# design.net
KiCad netlist of a schematic drawn in EasyEDA Pro
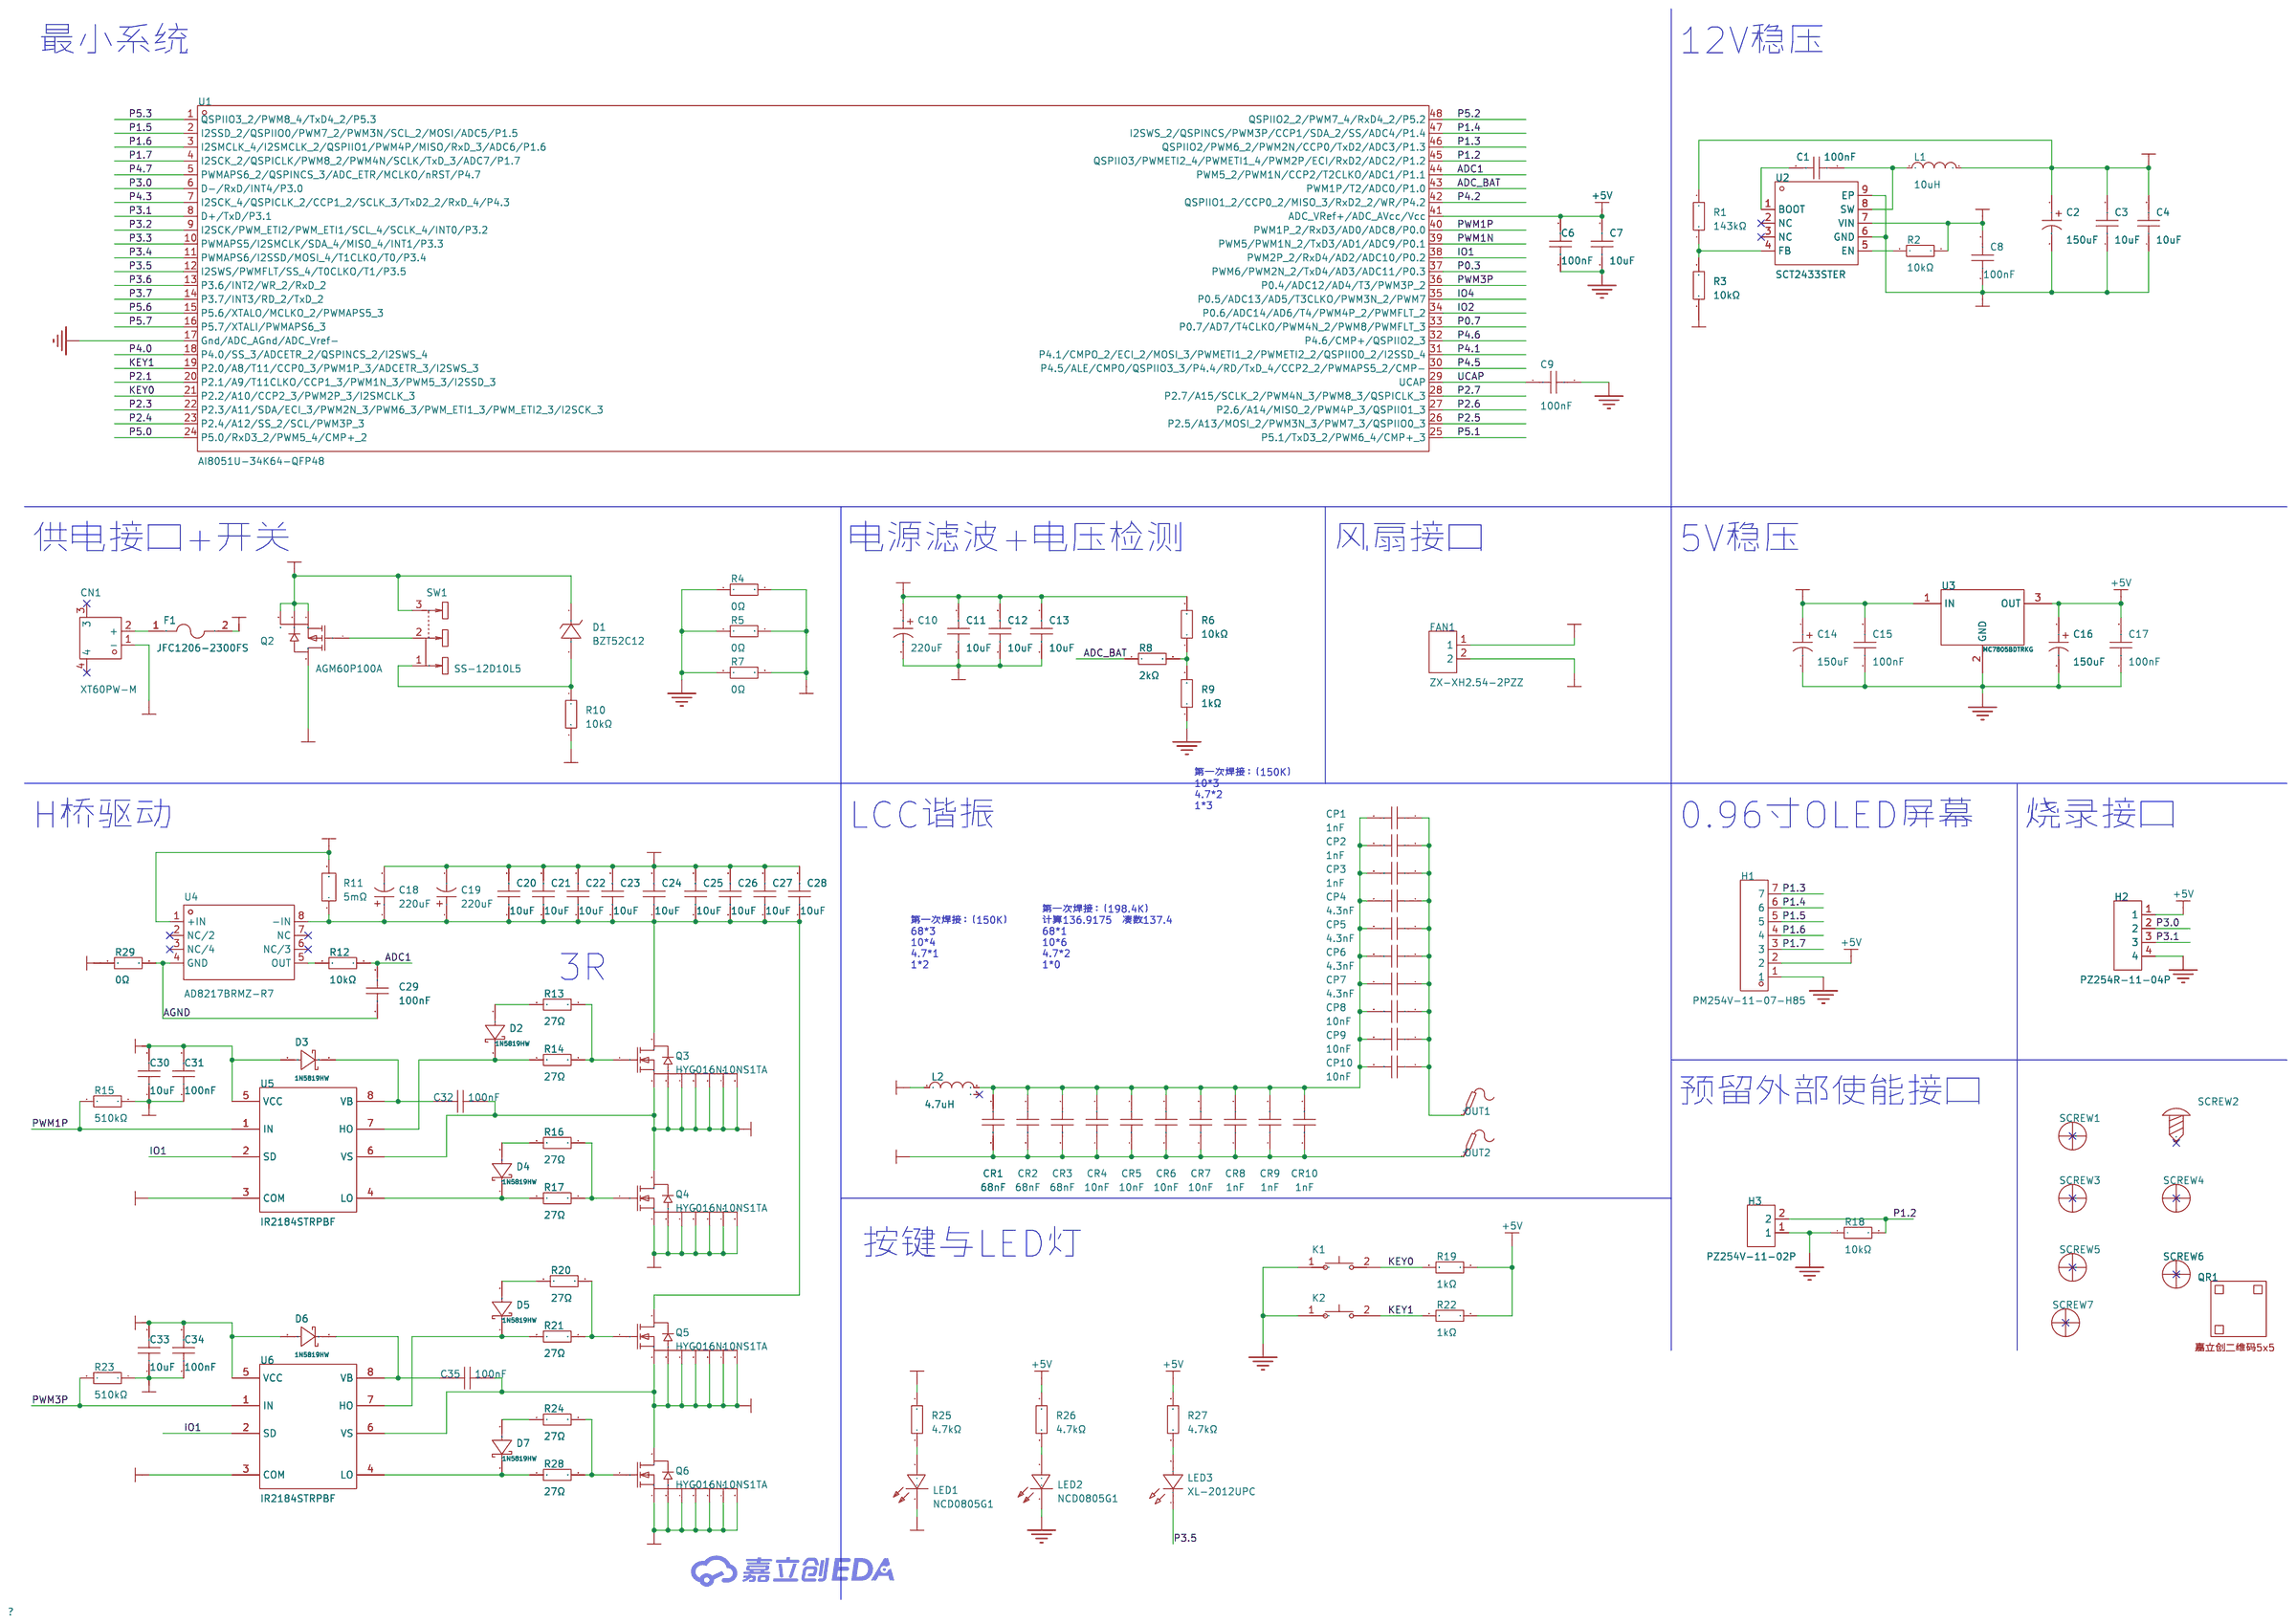
[diagram p0: schematic sheet]

(export (version "E")
  (design (tool "Eeschema 10.0.6"))
  (components
    (comp (ref "C1")
      (value "100nF")
      (fields
        (field (name "Manufacturer Part") "CC0603KRX7R9BB104")
        (field (name "Manufacturer") "YAGEO(国巨)")
      )
      (libsource (lib "easyedapro") (part "CC0603KRX7R9BB104"))
    )
    (comp (ref "C2")
      (value "150uF")
      (footprint "easyedapro:CAP-TH_BD6.3-P2.50-D0.5-FD")
      (description "容值:150uF;精度:±20%;额定电压:35V;纹波电流:2.55A;等效串联电阻:38mΩ;")
      (fields (field (name "Manufacturer Part") "HG1V157M0609PC") (field (name "Manufacturer") "HONOR(荣誉)"))
      (libsource (lib "easyedapro") (part "HG1V157M0609PC"))
    )
    (comp (ref "C3")
      (value "10uF")
      (footprint "easyedapro:C1206")
      (description "容值:10uF;精度:±10%;额定电压:50V;材质(温度系数):X5R;")
      (fields
        (field (name "Manufacturer Part") "GRM31CR61H106KA12L")
        (field (name "Manufacturer") "muRata(村田)")
      )
      (libsource (lib "easyedapro") (part "GRM31CR61H106KA12L"))
    )
    (comp (ref "C4")
      (value "10uF")
      (footprint "easyedapro:C1206")
      (description "容值:10uF;精度:±10%;额定电压:50V;材质(温度系数):X5R;")
      (fields
        (field (name "Manufacturer Part") "GRM31CR61H106KA12L")
        (field (name "Manufacturer") "muRata(村田)")
      )
      (libsource (lib "easyedapro") (part "GRM31CR61H106KA12L"))
    )
    (comp (ref "C6")
      (value "100nF")
      (footprint "easyedapro:C0603")
      (description "容值:100nF;精度:±10%;额定电压:50V;材质(温度系数):X7R;")
      (fields
        (field (name "Manufacturer Part") "CC0603KRX7R9BB104")
        (field (name "Manufacturer") "YAGEO(国巨)")
      )
      (libsource (lib "easyedapro") (part "CC0603KRX7R9BB104"))
    )
    (comp (ref "C7")
      (value "10uF")
      (footprint "easyedapro:C1206")
      (description "容值:10uF;精度:±10%;额定电压:50V;材质(温度系数):X5R;")
      (fields
        (field (name "Manufacturer Part") "GRM31CR61H106KA12L")
        (field (name "Manufacturer") "muRata(村田)")
      )
      (libsource (lib "easyedapro") (part "GRM31CR61H106KA12L"))
    )
    (comp (ref "C8")
      (value "100nF")
      (fields
        (field (name "Manufacturer Part") "CC0603KRX7R9BB104")
        (field (name "Manufacturer") "YAGEO(国巨)")
      )
      (libsource (lib "easyedapro") (part "CC0603KRX7R9BB104"))
    )
    (comp (ref "C9")
      (value "100nF")
      (footprint "easyedapro:C0603")
      (description "容值:100nF;精度:±10%;额定电压:50V;材质(温度系数):X7R;")
      (fields
        (field (name "Manufacturer Part") "CC0603KRX7R9BB104")
        (field (name "Manufacturer") "YAGEO(国巨)")
      )
      (libsource (lib "easyedapro") (part "CC0603KRX7R9BB104"))
    )
    (comp (ref "C10")
      (value "220uF")
      (footprint "easyedapro:CAP-TH_BD8.0-P3.50-D0.6-FD")
      (description "容值:220uF;精度:±20%;额定电压:35V;纹波电流:2.9A@100Hz;等效串联电阻(ESR):28mΩ@100kHz;类型:-;")
      (fields (field (name "Manufacturer Part") "PA35V220M8x8") (field (name "Manufacturer") "捷而瑞"))
      (libsource (lib "easyedapro") (part "PA35V220M8X8"))
    )
    (comp (ref "C11")
      (value "10uF")
      (footprint "easyedapro:C1206")
      (description "容值:10uF;精度:±10%;额定电压:50V;材质(温度系数):X5R;")
      (fields
        (field (name "Manufacturer Part") "GRM31CR61H106KA12L")
        (field (name "Manufacturer") "muRata(村田)")
      )
      (libsource (lib "easyedapro") (part "GRM31CR61H106KA12L"))
    )
    (comp (ref "C12")
      (value "10uF")
      (footprint "easyedapro:C1206")
      (description "容值:10uF;精度:±10%;额定电压:50V;材质(温度系数):X5R;")
      (fields
        (field (name "Manufacturer Part") "GRM31CR61H106KA12L")
        (field (name "Manufacturer") "muRata(村田)")
      )
      (libsource (lib "easyedapro") (part "GRM31CR61H106KA12L"))
    )
    (comp (ref "C13")
      (value "10uF")
      (footprint "easyedapro:C1206")
      (description "容值:10uF;精度:±10%;额定电压:50V;材质(温度系数):X5R;")
      (fields
        (field (name "Manufacturer Part") "GRM31CR61H106KA12L")
        (field (name "Manufacturer") "muRata(村田)")
      )
      (libsource (lib "easyedapro") (part "GRM31CR61H106KA12L"))
    )
    (comp (ref "C14")
      (value "150uF")
      (footprint "easyedapro:CAP-TH_BD6.3-P2.50-D0.5-FD")
      (description "容值:150uF;精度:±20%;额定电压:35V;纹波电流:2.55A;等效串联电阻:38mΩ;")
      (fields (field (name "Manufacturer Part") "HG1V157M0609PC") (field (name "Manufacturer") "HONOR(荣誉)"))
      (libsource (lib "easyedapro") (part "HG1V157M0609PC"))
    )
    (comp (ref "C15")
      (value "100nF")
      (footprint "easyedapro:C0603")
      (description "容值:100nF;精度:±10%;额定电压:50V;材质(温度系数):X7R;")
      (fields
        (field (name "Manufacturer Part") "CC0603KRX7R9BB104")
        (field (name "Manufacturer") "YAGEO(国巨)")
      )
      (libsource (lib "easyedapro") (part "CC0603KRX7R9BB104"))
    )
    (comp (ref "C16")
      (value "150uF")
      (footprint "easyedapro:CAP-TH_BD6.3-P2.50-D0.5-FD")
      (description "容值:150uF;精度:±20%;额定电压:35V;纹波电流:2.55A;等效串联电阻:38mΩ;")
      (fields (field (name "Manufacturer Part") "HG1V157M0609PC") (field (name "Manufacturer") "HONOR(荣誉)"))
      (libsource (lib "easyedapro") (part "HG1V157M0609PC"))
    )
    (comp (ref "C17")
      (value "100nF")
      (footprint "easyedapro:C0603")
      (description "容值:100nF;精度:±10%;额定电压:50V;材质(温度系数):X7R;")
      (fields
        (field (name "Manufacturer Part") "CC0603KRX7R9BB104")
        (field (name "Manufacturer") "YAGEO(国巨)")
      )
      (libsource (lib "easyedapro") (part "CC0603KRX7R9BB104"))
    )
    (comp (ref "C18")
      (value "220uF")
      (footprint "easyedapro:CAP-TH_BD8.0-P3.50-D0.6-FD")
      (description "容值:220uF;精度:±20%;额定电压:35V;纹波电流:2.9A@100Hz;等效串联电阻(ESR):28mΩ@100kHz;类型:-;")
      (fields (field (name "Manufacturer Part") "PA35V220M8x8") (field (name "Manufacturer") "捷而瑞"))
      (libsource (lib "easyedapro") (part "PA35V220M8X8"))
    )
    (comp (ref "C19")
      (value "220uF")
      (footprint "easyedapro:CAP-TH_BD8.0-P3.50-D0.6-FD")
      (description "容值:220uF;精度:±20%;额定电压:35V;纹波电流:2.9A@100Hz;等效串联电阻(ESR):28mΩ@100kHz;类型:-;")
      (fields (field (name "Manufacturer Part") "PA35V220M8x8") (field (name "Manufacturer") "捷而瑞"))
      (libsource (lib "easyedapro") (part "PA35V220M8X8"))
    )
    (comp (ref "C20")
      (value "10uF")
      (footprint "easyedapro:C1206")
      (description "容值:10uF;精度:±10%;额定电压:50V;材质(温度系数):X5R;")
      (fields
        (field (name "Manufacturer Part") "GRM31CR61H106KA12L")
        (field (name "Manufacturer") "muRata(村田)")
      )
      (libsource (lib "easyedapro") (part "GRM31CR61H106KA12L"))
    )
    (comp (ref "C21")
      (value "10uF")
      (footprint "easyedapro:C1206")
      (description "容值:10uF;精度:±10%;额定电压:50V;材质(温度系数):X5R;")
      (fields
        (field (name "Manufacturer Part") "GRM31CR61H106KA12L")
        (field (name "Manufacturer") "muRata(村田)")
      )
      (libsource (lib "easyedapro") (part "GRM31CR61H106KA12L"))
    )
    (comp (ref "C22")
      (value "10uF")
      (footprint "easyedapro:C1206")
      (description "容值:10uF;精度:±10%;额定电压:50V;材质(温度系数):X5R;")
      (fields
        (field (name "Manufacturer Part") "GRM31CR61H106KA12L")
        (field (name "Manufacturer") "muRata(村田)")
      )
      (libsource (lib "easyedapro") (part "GRM31CR61H106KA12L"))
    )
    (comp (ref "C23")
      (value "10uF")
      (footprint "easyedapro:C1206")
      (description "容值:10uF;精度:±10%;额定电压:50V;材质(温度系数):X5R;")
      (fields
        (field (name "Manufacturer Part") "GRM31CR61H106KA12L")
        (field (name "Manufacturer") "muRata(村田)")
      )
      (libsource (lib "easyedapro") (part "GRM31CR61H106KA12L"))
    )
    (comp (ref "C24")
      (value "10uF")
      (footprint "easyedapro:C1206")
      (description "容值:10uF;精度:±10%;额定电压:50V;材质(温度系数):X5R;")
      (fields
        (field (name "Manufacturer Part") "GRM31CR61H106KA12L")
        (field (name "Manufacturer") "muRata(村田)")
      )
      (libsource (lib "easyedapro") (part "GRM31CR61H106KA12L"))
    )
    (comp (ref "C25")
      (value "10uF")
      (footprint "easyedapro:C1206")
      (description "容值:10uF;精度:±10%;额定电压:50V;材质(温度系数):X5R;")
      (fields
        (field (name "Manufacturer Part") "GRM31CR61H106KA12L")
        (field (name "Manufacturer") "muRata(村田)")
      )
      (libsource (lib "easyedapro") (part "GRM31CR61H106KA12L"))
    )
    (comp (ref "C26")
      (value "10uF")
      (footprint "easyedapro:C1206")
      (description "容值:10uF;精度:±10%;额定电压:50V;材质(温度系数):X5R;")
      (fields
        (field (name "Manufacturer Part") "GRM31CR61H106KA12L")
        (field (name "Manufacturer") "muRata(村田)")
      )
      (libsource (lib "easyedapro") (part "GRM31CR61H106KA12L"))
    )
    (comp (ref "C27")
      (value "10uF")
      (footprint "easyedapro:C1206")
      (description "容值:10uF;精度:±10%;额定电压:50V;材质(温度系数):X5R;")
      (fields
        (field (name "Manufacturer Part") "GRM31CR61H106KA12L")
        (field (name "Manufacturer") "muRata(村田)")
      )
      (libsource (lib "easyedapro") (part "GRM31CR61H106KA12L"))
    )
    (comp (ref "C28")
      (value "10uF")
      (footprint "easyedapro:C1206")
      (description "容值:10uF;精度:±10%;额定电压:50V;材质(温度系数):X5R;")
      (fields
        (field (name "Manufacturer Part") "GRM31CR61H106KA12L")
        (field (name "Manufacturer") "muRata(村田)")
      )
      (libsource (lib "easyedapro") (part "GRM31CR61H106KA12L"))
    )
    (comp (ref "C29")
      (value "100nF")
      (footprint "easyedapro:C0603")
      (description "容值:100nF;精度:±10%;额定电压:50V;材质(温度系数):X7R;")
      (fields
        (field (name "Manufacturer Part") "CC0603KRX7R9BB104")
        (field (name "Manufacturer") "YAGEO(国巨)")
      )
      (libsource (lib "easyedapro") (part "CC0603KRX7R9BB104"))
    )
    (comp (ref "C30")
      (value "10uF")
      (footprint "easyedapro:C1206")
      (description "容值:10uF;精度:±10%;额定电压:50V;材质(温度系数):X5R;")
      (fields
        (field (name "Manufacturer Part") "GRM31CR61H106KA12L")
        (field (name "Manufacturer") "muRata(村田)")
      )
      (libsource (lib "easyedapro") (part "GRM31CR61H106KA12L"))
    )
    (comp (ref "C31")
      (value "100nF")
      (footprint "easyedapro:C0603")
      (description "容值:100nF;精度:±10%;额定电压:50V;材质(温度系数):X7R;")
      (fields
        (field (name "Manufacturer Part") "CC0603KRX7R9BB104")
        (field (name "Manufacturer") "YAGEO(国巨)")
      )
      (libsource (lib "easyedapro") (part "CC0603KRX7R9BB104"))
    )
    (comp (ref "C32")
      (value "100nF")
      (footprint "easyedapro:C0603")
      (description "容值:100nF;精度:±10%;额定电压:50V;材质(温度系数):X7R;")
      (fields
        (field (name "Manufacturer Part") "CC0603KRX7R9BB104")
        (field (name "Manufacturer") "YAGEO(国巨)")
      )
      (libsource (lib "easyedapro") (part "CC0603KRX7R9BB104"))
    )
    (comp (ref "C33")
      (value "10uF")
      (footprint "easyedapro:C1206")
      (description "容值:10uF;精度:±10%;额定电压:50V;材质(温度系数):X5R;")
      (fields
        (field (name "Manufacturer Part") "GRM31CR61H106KA12L")
        (field (name "Manufacturer") "muRata(村田)")
      )
      (libsource (lib "easyedapro") (part "GRM31CR61H106KA12L"))
    )
    (comp (ref "C34")
      (value "100nF")
      (footprint "easyedapro:C0603")
      (description "容值:100nF;精度:±10%;额定电压:50V;材质(温度系数):X7R;")
      (fields
        (field (name "Manufacturer Part") "CC0603KRX7R9BB104")
        (field (name "Manufacturer") "YAGEO(国巨)")
      )
      (libsource (lib "easyedapro") (part "CC0603KRX7R9BB104"))
    )
    (comp (ref "C35")
      (value "100nF")
      (footprint "easyedapro:C0603")
      (description "容值:100nF;精度:±10%;额定电压:50V;材质(温度系数):X7R;")
      (fields
        (field (name "Manufacturer Part") "CC0603KRX7R9BB104")
        (field (name "Manufacturer") "YAGEO(国巨)")
      )
      (libsource (lib "easyedapro") (part "CC0603KRX7R9BB104"))
    )
    (comp (ref "CN1")
      (value "XT60PW-M")
      (footprint "easyedapro:CONN-TH_XT60PW-M")
      (description "类别:-;类型1:-;")
      (fields (field (name "Manufacturer") "AMASS(艾迈斯)"))
      (libsource (lib "easyedapro") (part "XT60PW-M"))
    )
    (comp (ref "CP1")
      (value "1nF")
      (footprint "easyedapro:C1206")
      (description "容值:1nF;精度:±5%;额定电压:1kV;材质(温度系数):NP0;")
      (fields
        (field (name "Manufacturer Part") "CC1206JKNPOCBN102")
        (field (name "Manufacturer") "YAGEO(国巨)")
      )
      (libsource (lib "easyedapro") (part "CC1206JKNPOCBN102"))
    )
    (comp (ref "CP2")
      (value "1nF")
      (footprint "easyedapro:C1206")
      (description "容值:1nF;精度:±5%;额定电压:1kV;材质(温度系数):NP0;")
      (fields
        (field (name "Manufacturer Part") "CC1206JKNPOCBN102")
        (field (name "Manufacturer") "YAGEO(国巨)")
      )
      (libsource (lib "easyedapro") (part "CC1206JKNPOCBN102"))
    )
    (comp (ref "CP3")
      (value "1nF")
      (footprint "easyedapro:C1206")
      (description "容值:1nF;精度:±5%;额定电压:1kV;材质(温度系数):NP0;")
      (fields
        (field (name "Manufacturer Part") "CC1206JKNPOCBN102")
        (field (name "Manufacturer") "YAGEO(国巨)")
      )
      (libsource (lib "easyedapro") (part "CC1206JKNPOCBN102"))
    )
    (comp (ref "CP4")
      (value "4.3nF")
      (footprint "easyedapro:C1206")
      (description "容值:4.3nF;精度:±5%;额定电压:100V;材质(温度系数):C0G;")
      (fields
        (field (name "Manufacturer Part") "GRM3195C2A432JA01D")
        (field (name "Manufacturer") "muRata(村田)")
      )
      (libsource (lib "easyedapro") (part "GRM3195C2A432JA01D"))
    )
    (comp (ref "CP5")
      (value "4.3nF")
      (footprint "easyedapro:C1206")
      (description "容值:4.3nF;精度:±5%;额定电压:100V;材质(温度系数):C0G;")
      (fields
        (field (name "Manufacturer Part") "GRM3195C2A432JA01D")
        (field (name "Manufacturer") "muRata(村田)")
      )
      (libsource (lib "easyedapro") (part "GRM3195C2A432JA01D"))
    )
    (comp (ref "CP6")
      (value "4.3nF")
      (footprint "easyedapro:C1206")
      (description "容值:4.3nF;精度:±5%;额定电压:100V;材质(温度系数):C0G;")
      (fields
        (field (name "Manufacturer Part") "GRM3195C2A432JA01D")
        (field (name "Manufacturer") "muRata(村田)")
      )
      (libsource (lib "easyedapro") (part "GRM3195C2A432JA01D"))
    )
    (comp (ref "CP7")
      (value "4.3nF")
      (footprint "easyedapro:C1206")
      (description "容值:4.3nF;精度:±5%;额定电压:100V;材质(温度系数):C0G;")
      (fields
        (field (name "Manufacturer Part") "GRM3195C2A432JA01D")
        (field (name "Manufacturer") "muRata(村田)")
      )
      (libsource (lib "easyedapro") (part "GRM3195C2A432JA01D"))
    )
    (comp (ref "CP8")
      (value "10nF")
      (footprint "easyedapro:C1206")
      (description "容值:10nF;精度:±5%;额定电压:100V;材质(温度系数):C0G;")
      (fields
        (field (name "Manufacturer Part") "GCM3195C2A103JA16D")
        (field (name "Manufacturer") "muRata(村田)")
      )
      (libsource (lib "easyedapro") (part "GCM3195C2A103JA16D"))
    )
    (comp (ref "CP9")
      (value "10nF")
      (footprint "easyedapro:C1206")
      (description "容值:10nF;精度:±5%;额定电压:100V;材质(温度系数):C0G;")
      (fields
        (field (name "Manufacturer Part") "GCM3195C2A103JA16D")
        (field (name "Manufacturer") "muRata(村田)")
      )
      (libsource (lib "easyedapro") (part "GCM3195C2A103JA16D"))
    )
    (comp (ref "CP10")
      (value "10nF")
      (footprint "easyedapro:C1206")
      (description "容值:10nF;精度:±5%;额定电压:100V;材质(温度系数):C0G;")
      (fields
        (field (name "Manufacturer Part") "GCM3195C2A103JA16D")
        (field (name "Manufacturer") "muRata(村田)")
      )
      (libsource (lib "easyedapro") (part "GCM3195C2A103JA16D"))
    )
    (comp (ref "CR1")
      (value "68nF")
      (footprint "easyedapro:C1206")
      (description "容值:68nF;精度:±5%;额定电压:100V;温度系数:C0G;")
      (fields (field (name "Manufacturer Part") "C3216C0G2A683JT000E") (field (name "Manufacturer") "TDK"))
      (libsource (lib "easyedapro") (part "C3216C0G2A683JT000E"))
    )
    (comp (ref "CR2")
      (value "68nF")
      (footprint "easyedapro:C1206")
      (description "容值:68nF;精度:±5%;额定电压:100V;温度系数:C0G;")
      (fields (field (name "Manufacturer Part") "C3216C0G2A683JT000E") (field (name "Manufacturer") "TDK"))
      (libsource (lib "easyedapro") (part "C3216C0G2A683JT000E"))
    )
    (comp (ref "CR3")
      (value "68nF")
      (footprint "easyedapro:C1206")
      (description "容值:68nF;精度:±5%;额定电压:100V;温度系数:C0G;")
      (fields (field (name "Manufacturer Part") "C3216C0G2A683JT000E") (field (name "Manufacturer") "TDK"))
      (libsource (lib "easyedapro") (part "C3216C0G2A683JT000E"))
    )
    (comp (ref "CR4")
      (value "10nF")
      (footprint "easyedapro:C1206")
      (description "容值:10nF;精度:±5%;额定电压:100V;材质(温度系数):C0G;")
      (fields
        (field (name "Manufacturer Part") "GCM3195C2A103JA16D")
        (field (name "Manufacturer") "muRata(村田)")
      )
      (libsource (lib "easyedapro") (part "GCM3195C2A103JA16D"))
    )
    (comp (ref "CR5")
      (value "10nF")
      (footprint "easyedapro:C1206")
      (description "容值:10nF;精度:±5%;额定电压:100V;材质(温度系数):C0G;")
      (fields
        (field (name "Manufacturer Part") "GCM3195C2A103JA16D")
        (field (name "Manufacturer") "muRata(村田)")
      )
      (libsource (lib "easyedapro") (part "GCM3195C2A103JA16D"))
    )
    (comp (ref "CR6")
      (value "10nF")
      (footprint "easyedapro:C1206")
      (description "容值:10nF;精度:±5%;额定电压:100V;材质(温度系数):C0G;")
      (fields
        (field (name "Manufacturer Part") "GCM3195C2A103JA16D")
        (field (name "Manufacturer") "muRata(村田)")
      )
      (libsource (lib "easyedapro") (part "GCM3195C2A103JA16D"))
    )
    (comp (ref "CR7")
      (value "10nF")
      (footprint "easyedapro:C1206")
      (description "容值:10nF;精度:±5%;额定电压:100V;材质(温度系数):C0G;")
      (fields
        (field (name "Manufacturer Part") "GCM3195C2A103JA16D")
        (field (name "Manufacturer") "muRata(村田)")
      )
      (libsource (lib "easyedapro") (part "GCM3195C2A103JA16D"))
    )
    (comp (ref "CR8")
      (value "1nF")
      (footprint "easyedapro:C1206")
      (description "容值:1nF;精度:±5%;额定电压:1kV;材质(温度系数):NP0;")
      (fields
        (field (name "Manufacturer Part") "CC1206JKNPOCBN102")
        (field (name "Manufacturer") "YAGEO(国巨)")
      )
      (libsource (lib "easyedapro") (part "CC1206JKNPOCBN102"))
    )
    (comp (ref "CR9")
      (value "1nF")
      (footprint "easyedapro:C1206")
      (description "容值:1nF;精度:±5%;额定电压:1kV;材质(温度系数):NP0;")
      (fields
        (field (name "Manufacturer Part") "CC1206JKNPOCBN102")
        (field (name "Manufacturer") "YAGEO(国巨)")
      )
      (libsource (lib "easyedapro") (part "CC1206JKNPOCBN102"))
    )
    (comp (ref "CR10")
      (value "1nF")
      (footprint "easyedapro:C1206")
      (description "容值:1nF;精度:±5%;额定电压:1kV;材质(温度系数):NP0;")
      (fields
        (field (name "Manufacturer Part") "CC1206JKNPOCBN102")
        (field (name "Manufacturer") "YAGEO(国巨)")
      )
      (libsource (lib "easyedapro") (part "CC1206JKNPOCBN102"))
    )
    (comp (ref "D1")
      (value "BZT52C12")
      (footprint "easyedapro:SOD-123_L2.7-W1.6-LS3.7-RD")
      (description "二极管配置:独立式;稳压值(标称值):12V;稳压值(范围):11.4V~12.6V;功率(Pd):500mW;")
      (fields (field (name "Manufacturer") "宏迦橙"))
      (libsource (lib "easyedapro") (part "BZT52C12_C19077410"))
    )
    (comp (ref "D2")
      (value "1N5819HW")
      (footprint "easyedapro:SOD-123_L2.7-W1.6-LS3.8-RD")
      (description "正向压降(Vf):580mV@1.0A;直流反向耐压(Vr):40V;整流电流:1A;")
      (fields (field (name "Manufacturer") "GOODWORK(固得沃克)"))
      (libsource (lib "easyedapro") (part "1N5819HW_C41431974"))
    )
    (comp (ref "D3")
      (value "1N5819HW")
      (footprint "easyedapro:SOD-123_L2.7-W1.6-LS3.8-RD")
      (description "正向压降(Vf):580mV@1.0A;直流反向耐压(Vr):40V;整流电流:1A;")
      (fields (field (name "Manufacturer") "GOODWORK(固得沃克)"))
      (libsource (lib "easyedapro") (part "1N5819HW_C41431974"))
    )
    (comp (ref "D4")
      (value "1N5819HW")
      (footprint "easyedapro:SOD-123_L2.7-W1.6-LS3.8-RD")
      (description "正向压降(Vf):580mV@1.0A;直流反向耐压(Vr):40V;整流电流:1A;")
      (fields (field (name "Manufacturer") "GOODWORK(固得沃克)"))
      (libsource (lib "easyedapro") (part "1N5819HW_C41431974"))
    )
    (comp (ref "D5")
      (value "1N5819HW")
      (footprint "easyedapro:SOD-123_L2.7-W1.6-LS3.8-RD")
      (description "正向压降(Vf):580mV@1.0A;直流反向耐压(Vr):40V;整流电流:1A;")
      (fields (field (name "Manufacturer") "GOODWORK(固得沃克)"))
      (libsource (lib "easyedapro") (part "1N5819HW_C41431974"))
    )
    (comp (ref "D6")
      (value "1N5819HW")
      (footprint "easyedapro:SOD-123_L2.7-W1.6-LS3.8-RD")
      (description "正向压降(Vf):580mV@1.0A;直流反向耐压(Vr):40V;整流电流:1A;")
      (fields (field (name "Manufacturer") "GOODWORK(固得沃克)"))
      (libsource (lib "easyedapro") (part "1N5819HW_C41431974"))
    )
    (comp (ref "D7")
      (value "1N5819HW")
      (footprint "easyedapro:SOD-123_L2.7-W1.6-LS3.8-RD")
      (description "正向压降(Vf):580mV@1.0A;直流反向耐压(Vr):40V;整流电流:1A;")
      (fields (field (name "Manufacturer") "GOODWORK(固得沃克)"))
      (libsource (lib "easyedapro") (part "1N5819HW_C41431974"))
    )
    (comp (ref "F1")
      (value "JFC1206-2300FS")
      (footprint "easyedapro:F1206")
      (description "类型:贴片式保险丝;额定电流:30A;额定电压 (AC):32V;额定电压:32V;分断能力:150A;")
      (fields (field (name "Manufacturer") "JDTfuse(集电通)"))
      (libsource (lib "easyedapro") (part "JFC1206-2300FS"))
    )
    (comp (ref "FAN1")
      (value "ZX-XH2.54-2PZZ")
      (footprint "easyedapro:CONN-TH_2P-P2.50_HX25003-2A")
      (fields (field (name "Manufacturer") "Megastar(兆星)"))
      (libsource (lib "easyedapro") (part "ZX-XH2.54-2PZZ"))
    )
    (comp (ref "H1")
      (value "PM254V-11-07-H85")
      (footprint "easyedapro:HDR-TH_7P-P2.54-V-F")
      (fields (field (name "Manufacturer") "XFCN(兴飞)"))
      (libsource (lib "easyedapro") (part "PM254V-11-07-H85"))
    )
    (comp (ref "H2")
      (value "PZ254R-11-04P")
      (footprint "easyedapro:HDR-TH_4P-P2.54-H-M-W10.4")
      (fields (field (name "Manufacturer") "XFCN(兴飞)"))
      (libsource (lib "easyedapro") (part "PZ254R-11-04P"))
    )
    (comp (ref "H3")
      (value "PZ254V-11-02P")
      (footprint "easyedapro:HDR-TH_2P-P2.54-V-M")
      (fields (field (name "Manufacturer") "XFCN(兴飞)"))
      (libsource (lib "easyedapro") (part "PZ254V-11-02P"))
    )
    (comp (ref "K1")
      (value "TS3625A")
      (footprint "easyedapro:KEY-SMD_L6.0-W3.5-LS8.4")
      (fields (field (name "Manufacturer") "SHOU HAN(首韩)"))
      (libsource (lib "easyedapro") (part "TS3625A"))
    )
    (comp (ref "K2")
      (value "TS3625A")
      (footprint "easyedapro:KEY-SMD_L6.0-W3.5-LS8.4")
      (fields (field (name "Manufacturer") "SHOU HAN(首韩)"))
      (libsource (lib "easyedapro") (part "TS3625A"))
    )
    (comp (ref "L1")
      (value "10uH")
      (footprint "easyedapro:IND-SMD_L4.1-W4.1_FTC404020S")
      (description "电感值:10uH;精度:±20%;额定电流:3.4A;饱和电流(Isat):4.9A;类型:一体成型电感;")
      (fields
        (field (name "Manufacturer Part") "FTC404020S100MGCA")
        (field (name "Manufacturer") "cjiang(长江微电)")
      )
      (libsource (lib "easyedapro") (part "FTC404020S100MGCA"))
    )
    (comp (ref "L2")
      (value "4.7uH")
      (footprint "easyedapro:IND-SMD_3P-L28.0-W19.0-LS27.0")
      (description "电感值:4.7uH;精度:±20%;额定电流:47.5A;饱和电流(Isat):49.5A;类型:扁平线大电流电感;")
      (fields
        (field (name "Manufacturer Part") "RSBPQ2918-4R7M")
        (field (name "Manufacturer") "Ruishen(瑞申电子)")
      )
      (libsource (lib "easyedapro") (part "RSBPQ2918-4R7M"))
    )
    (comp (ref "LED1")
      (value "NCD0805G1")
      (footprint "easyedapro:LED0805-R-RD")
      (fields (field (name "Manufacturer") "国星光电"))
      (libsource (lib "easyedapro") (part "FC-2012UGK-520D5"))
    )
    (comp (ref "LED2")
      (value "NCD0805G1")
      (footprint "easyedapro:LED0805-R-RD")
      (fields (field (name "Manufacturer") "国星光电"))
      (libsource (lib "easyedapro") (part "FC-2012UGK-520D5"))
    )
    (comp (ref "LED3")
      (value "XL-2012UPC")
      (footprint "easyedapro:LED0805-RD_PINK")
      (fields (field (name "Manufacturer") "XINGLIGHT(成兴光)"))
      (libsource (lib "easyedapro") (part "XL-2012UPC"))
    )
    (comp (ref "OUT1")
      (value "~")
      (footprint "easyedapro:Test-Point-0.5mm")
      (description "Test Point 测试点")
      (libsource (lib "easyedapro") (part "Test-Point"))
    )
    (comp (ref "OUT2")
      (value "~")
      (footprint "easyedapro:Test-Point-0.5mm")
      (description "Test Point 测试点")
      (libsource (lib "easyedapro") (part "Test-Point"))
    )
    (comp (ref "Q2")
      (value "AGM60P100A")
      (footprint "easyedapro:TDSON-8_L5.9-W5.2-P1.27-BL")
      (fields (field (name "Manufacturer") "AGM-Semi(芯控源)"))
      (libsource (lib "easyedapro") (part "AGM60P100A"))
    )
    (comp (ref "Q3")
      (value "HYG016N10NS1TA")
      (footprint "easyedapro:TOLL-8_L10.4-W9.9-P1.20-LS11.7-BL")
      (fields (field (name "Manufacturer") "HUAYI(华羿微)"))
      (libsource (lib "easyedapro") (part "HYG016N10NS1TA"))
    )
    (comp (ref "Q4")
      (value "HYG016N10NS1TA")
      (footprint "easyedapro:TOLL-8_L10.4-W9.9-P1.20-LS11.7-BL")
      (fields (field (name "Manufacturer") "HUAYI(华羿微)"))
      (libsource (lib "easyedapro") (part "HYG016N10NS1TA"))
    )
    (comp (ref "Q5")
      (value "HYG016N10NS1TA")
      (footprint "easyedapro:TOLL-8_L10.4-W9.9-P1.20-LS11.7-BL")
      (fields (field (name "Manufacturer") "HUAYI(华羿微)"))
      (libsource (lib "easyedapro") (part "HYG016N10NS1TA"))
    )
    (comp (ref "Q6")
      (value "HYG016N10NS1TA")
      (footprint "easyedapro:TOLL-8_L10.4-W9.9-P1.20-LS11.7-BL")
      (fields (field (name "Manufacturer") "HUAYI(华羿微)"))
      (libsource (lib "easyedapro") (part "HYG016N10NS1TA"))
    )
    (comp (ref "QR1")
      (value "~")
      (footprint "easyedapro:JLC-QRCODE-5x5")
      (libsource (lib "easyedapro") (part "嘉立创二维码5x5"))
    )
    (comp (ref "R1")
      (value "143kΩ")
      (footprint "easyedapro:R0603")
      (description "电阻类型:厚膜电阻;阻值:143kΩ;精度:±1%;功率:100mW;最大工作电压:75V;温度系数:±100ppm/°C;")
      (fields
        (field (name "Manufacturer Part") "0603WAF1433T5E")
        (field (name "Manufacturer") "UNI-ROYAL(厚声)")
      )
      (libsource (lib "easyedapro") (part "0603WAF1433T5E"))
    )
    (comp (ref "R2")
      (value "10kΩ")
      (footprint "easyedapro:R0603")
      (description "电阻类型:厚膜电阻;阻值:10kΩ;精度:±1%;功率:100mW;最大工作电压:75V;温度系数:±100ppm/°C;")
      (fields
        (field (name "Manufacturer Part") "0603WAF1002T5E")
        (field (name "Manufacturer") "UNI-ROYAL(厚声)")
      )
      (libsource (lib "easyedapro") (part "0603WAF1002T5E"))
    )
    (comp (ref "R3")
      (value "10kΩ")
      (footprint "easyedapro:R0603")
      (description "电阻类型:厚膜电阻;阻值:10kΩ;精度:±1%;功率:100mW;最大工作电压:75V;温度系数:±100ppm/°C;")
      (fields
        (field (name "Manufacturer Part") "0603WAF1002T5E")
        (field (name "Manufacturer") "UNI-ROYAL(厚声)")
      )
      (libsource (lib "easyedapro") (part "0603WAF1002T5E"))
    )
    (comp (ref "R4")
      (value "0Ω")
      (footprint "easyedapro:R0603")
      (description "电阻类型:厚膜电阻;阻值:0Ω;精度:±1%;功率:100mW;最大工作电压:75V;")
      (fields
        (field (name "Manufacturer Part") "0603WAF0000T5E")
        (field (name "Manufacturer") "UNI-ROYAL(厚声)")
      )
      (libsource (lib "easyedapro") (part "0603WAF0000T5E"))
    )
    (comp (ref "R5")
      (value "0Ω")
      (footprint "easyedapro:R0603")
      (description "电阻类型:厚膜电阻;阻值:0Ω;精度:±1%;功率:100mW;最大工作电压:75V;")
      (fields
        (field (name "Manufacturer Part") "0603WAF0000T5E")
        (field (name "Manufacturer") "UNI-ROYAL(厚声)")
      )
      (libsource (lib "easyedapro") (part "0603WAF0000T5E"))
    )
    (comp (ref "R6")
      (value "10kΩ")
      (footprint "easyedapro:R0603")
      (description "电阻类型:厚膜电阻;阻值:10kΩ;精度:±1%;功率:100mW;最大工作电压:75V;温度系数:±100ppm/°C;")
      (fields
        (field (name "Manufacturer Part") "0603WAF1002T5E")
        (field (name "Manufacturer") "UNI-ROYAL(厚声)")
      )
      (libsource (lib "easyedapro") (part "0603WAF1002T5E"))
    )
    (comp (ref "R7")
      (value "0Ω")
      (footprint "easyedapro:R0603")
      (description "电阻类型:厚膜电阻;阻值:0Ω;精度:±1%;功率:100mW;最大工作电压:75V;")
      (fields
        (field (name "Manufacturer Part") "0603WAF0000T5E")
        (field (name "Manufacturer") "UNI-ROYAL(厚声)")
      )
      (libsource (lib "easyedapro") (part "0603WAF0000T5E"))
    )
    (comp (ref "R8")
      (value "2kΩ")
      (footprint "easyedapro:R0603")
      (description "电阻类型:厚膜电阻;阻值:2kΩ;精度:±1%;功率:100mW;最大工作电压:75V;温度系数:±100ppm/°C;")
      (fields
        (field (name "Manufacturer Part") "0603WAF2001T5E")
        (field (name "Manufacturer") "UNI-ROYAL(厚声)")
      )
      (libsource (lib "easyedapro") (part "0603WAF2001T5E"))
    )
    (comp (ref "R9")
      (value "1kΩ")
      (footprint "easyedapro:R0603")
      (description "电阻类型:厚膜电阻;阻值:1kΩ;精度:±1%;功率:100mW;最大工作电压:75V;温度系数:±100ppm/°C;")
      (fields
        (field (name "Manufacturer Part") "0603WAF1001T5E")
        (field (name "Manufacturer") "UNI-ROYAL(厚声)")
      )
      (libsource (lib "easyedapro") (part "0603WAF1001T5E"))
    )
    (comp (ref "R10")
      (value "10kΩ")
      (footprint "easyedapro:R0603")
      (description "电阻类型:厚膜电阻;阻值:10kΩ;精度:±1%;功率:100mW;最大工作电压:75V;温度系数:±100ppm/°C;")
      (fields
        (field (name "Manufacturer Part") "0603WAF1002T5E")
        (field (name "Manufacturer") "UNI-ROYAL(厚声)")
      )
      (libsource (lib "easyedapro") (part "0603WAF1002T5E"))
    )
    (comp (ref "R11")
      (value "5mΩ")
      (footprint "easyedapro:RES-SMD_L10.0-W5.2")
      (description "阻值:5mΩ;功率:5W;")
      (fields
        (field (name "Manufacturer Part") "HolRS3921-5W-5mR-1%")
        (field (name "Manufacturer") "Milliohm(毫欧)")
      )
      (libsource (lib "easyedapro") (part "HOLRS3921-5W-5MR-1%"))
    )
    (comp (ref "R12")
      (value "10kΩ")
      (footprint "easyedapro:R0603")
      (description "电阻类型:厚膜电阻;阻值:10kΩ;精度:±1%;功率:100mW;最大工作电压:75V;温度系数:±100ppm/°C;")
      (fields
        (field (name "Manufacturer Part") "0603WAF1002T5E")
        (field (name "Manufacturer") "UNI-ROYAL(厚声)")
      )
      (libsource (lib "easyedapro") (part "0603WAF1002T5E"))
    )
    (comp (ref "R13")
      (value "27Ω")
      (footprint "easyedapro:R0805")
      (description "电阻类型:厚膜电阻;阻值:27Ω;精度:±1%;功率:125mW;最大工作电压:150V;温度系数:±100ppm/°C;")
      (fields
        (field (name "Manufacturer Part") "0805W8F270JT5E")
        (field (name "Manufacturer") "UNI-ROYAL(厚声)")
      )
      (libsource (lib "easyedapro") (part "0805W8F270JT5E"))
    )
    (comp (ref "R14")
      (value "27Ω")
      (footprint "easyedapro:R0805")
      (description "电阻类型:厚膜电阻;阻值:27Ω;精度:±1%;功率:125mW;最大工作电压:150V;温度系数:±100ppm/°C;")
      (fields
        (field (name "Manufacturer Part") "0805W8F270JT5E")
        (field (name "Manufacturer") "UNI-ROYAL(厚声)")
      )
      (libsource (lib "easyedapro") (part "0805W8F270JT5E"))
    )
    (comp (ref "R15")
      (value "510kΩ")
      (footprint "easyedapro:R0603")
      (description "电阻类型:厚膜电阻;阻值:510kΩ;精度:±1%;功率:100mW;最大工作电压:75V;温度系数:±100ppm/°C;")
      (fields
        (field (name "Manufacturer Part") "0603WAF5103T5E")
        (field (name "Manufacturer") "UNI-ROYAL(厚声)")
      )
      (libsource (lib "easyedapro") (part "0603WAF5103T5E"))
    )
    (comp (ref "R16")
      (value "27Ω")
      (footprint "easyedapro:R0805")
      (description "电阻类型:厚膜电阻;阻值:27Ω;精度:±1%;功率:125mW;最大工作电压:150V;温度系数:±100ppm/°C;")
      (fields
        (field (name "Manufacturer Part") "0805W8F270JT5E")
        (field (name "Manufacturer") "UNI-ROYAL(厚声)")
      )
      (libsource (lib "easyedapro") (part "0805W8F270JT5E"))
    )
    (comp (ref "R17")
      (value "27Ω")
      (footprint "easyedapro:R0805")
      (description "电阻类型:厚膜电阻;阻值:27Ω;精度:±1%;功率:125mW;最大工作电压:150V;温度系数:±100ppm/°C;")
      (fields
        (field (name "Manufacturer Part") "0805W8F270JT5E")
        (field (name "Manufacturer") "UNI-ROYAL(厚声)")
      )
      (libsource (lib "easyedapro") (part "0805W8F270JT5E"))
    )
    (comp (ref "R18")
      (value "10kΩ")
      (footprint "easyedapro:R0603")
      (description "电阻类型:厚膜电阻;阻值:10kΩ;精度:±1%;功率:100mW;最大工作电压:75V;温度系数:±100ppm/°C;")
      (fields
        (field (name "Manufacturer Part") "0603WAF1002T5E")
        (field (name "Manufacturer") "UNI-ROYAL(厚声)")
      )
      (libsource (lib "easyedapro") (part "0603WAF1002T5E"))
    )
    (comp (ref "R19")
      (value "1kΩ")
      (footprint "easyedapro:R0603")
      (description "电阻类型:厚膜电阻;阻值:1kΩ;精度:±1%;功率:100mW;最大工作电压:75V;温度系数:±100ppm/°C;")
      (fields
        (field (name "Manufacturer Part") "0603WAF1001T5E")
        (field (name "Manufacturer") "UNI-ROYAL(厚声)")
      )
      (libsource (lib "easyedapro") (part "0603WAF1001T5E"))
    )
    (comp (ref "R20")
      (value "27Ω")
      (footprint "easyedapro:R0805")
      (description "电阻类型:厚膜电阻;阻值:27Ω;精度:±1%;功率:125mW;最大工作电压:150V;温度系数:±100ppm/°C;")
      (fields
        (field (name "Manufacturer Part") "0805W8F270JT5E")
        (field (name "Manufacturer") "UNI-ROYAL(厚声)")
      )
      (libsource (lib "easyedapro") (part "0805W8F270JT5E"))
    )
    (comp (ref "R21")
      (value "27Ω")
      (footprint "easyedapro:R0805")
      (description "电阻类型:厚膜电阻;阻值:27Ω;精度:±1%;功率:125mW;最大工作电压:150V;温度系数:±100ppm/°C;")
      (fields
        (field (name "Manufacturer Part") "0805W8F270JT5E")
        (field (name "Manufacturer") "UNI-ROYAL(厚声)")
      )
      (libsource (lib "easyedapro") (part "0805W8F270JT5E"))
    )
    (comp (ref "R22")
      (value "1kΩ")
      (footprint "easyedapro:R0603")
      (description "电阻类型:厚膜电阻;阻值:1kΩ;精度:±1%;功率:100mW;最大工作电压:75V;温度系数:±100ppm/°C;")
      (fields
        (field (name "Manufacturer Part") "0603WAF1001T5E")
        (field (name "Manufacturer") "UNI-ROYAL(厚声)")
      )
      (libsource (lib "easyedapro") (part "0603WAF1001T5E"))
    )
    (comp (ref "R23")
      (value "510kΩ")
      (footprint "easyedapro:R0603")
      (description "电阻类型:厚膜电阻;阻值:510kΩ;精度:±1%;功率:100mW;最大工作电压:75V;温度系数:±100ppm/°C;")
      (fields
        (field (name "Manufacturer Part") "0603WAF5103T5E")
        (field (name "Manufacturer") "UNI-ROYAL(厚声)")
      )
      (libsource (lib "easyedapro") (part "0603WAF5103T5E"))
    )
    (comp (ref "R24")
      (value "27Ω")
      (footprint "easyedapro:R0805")
      (description "电阻类型:厚膜电阻;阻值:27Ω;精度:±1%;功率:125mW;最大工作电压:150V;温度系数:±100ppm/°C;")
      (fields
        (field (name "Manufacturer Part") "0805W8F270JT5E")
        (field (name "Manufacturer") "UNI-ROYAL(厚声)")
      )
      (libsource (lib "easyedapro") (part "0805W8F270JT5E"))
    )
    (comp (ref "R25")
      (value "4.7kΩ")
      (footprint "easyedapro:R0603")
      (description "电阻类型:厚膜电阻;阻值:4.7kΩ;精度:±1%;功率:100mW;最大工作电压:75V;温度系数:±100ppm/°C;")
      (fields (field (name "Manufacturer Part") "RC0603FR-074K7L") (field (name "Manufacturer") "YAGEO(国巨)"))
      (libsource (lib "easyedapro") (part "RC0603FR-074K7L"))
    )
    (comp (ref "R26")
      (value "4.7kΩ")
      (footprint "easyedapro:R0603")
      (description "电阻类型:厚膜电阻;阻值:4.7kΩ;精度:±1%;功率:100mW;最大工作电压:75V;温度系数:±100ppm/°C;")
      (fields (field (name "Manufacturer Part") "RC0603FR-074K7L") (field (name "Manufacturer") "YAGEO(国巨)"))
      (libsource (lib "easyedapro") (part "RC0603FR-074K7L"))
    )
    (comp (ref "R27")
      (value "4.7kΩ")
      (footprint "easyedapro:R0603")
      (description "电阻类型:厚膜电阻;阻值:4.7kΩ;精度:±1%;功率:100mW;最大工作电压:75V;温度系数:±100ppm/°C;")
      (fields (field (name "Manufacturer Part") "RC0603FR-074K7L") (field (name "Manufacturer") "YAGEO(国巨)"))
      (libsource (lib "easyedapro") (part "RC0603FR-074K7L"))
    )
    (comp (ref "R28")
      (value "27Ω")
      (footprint "easyedapro:R0805")
      (description "电阻类型:厚膜电阻;阻值:27Ω;精度:±1%;功率:125mW;最大工作电压:150V;温度系数:±100ppm/°C;")
      (fields
        (field (name "Manufacturer Part") "0805W8F270JT5E")
        (field (name "Manufacturer") "UNI-ROYAL(厚声)")
      )
      (libsource (lib "easyedapro") (part "0805W8F270JT5E"))
    )
    (comp (ref "R29")
      (value "0Ω")
      (footprint "easyedapro:R0603")
      (description "电阻类型:厚膜电阻;阻值:0Ω;精度:±1%;功率:100mW;最大工作电压:75V;")
      (fields
        (field (name "Manufacturer Part") "0603WAF0000T5E")
        (field (name "Manufacturer") "UNI-ROYAL(厚声)")
      )
      (libsource (lib "easyedapro") (part "0603WAF0000T5E"))
    )
    (comp (ref "SCREW1")
      (value "~")
      (footprint "easyedapro:M3螺丝")
      (libsource (lib "easyedapro") (part "M3螺丝"))
    )
    (comp (ref "SCREW2")
      (value "~")
      (footprint "easyedapro:M3螺丝")
      (libsource (lib "easyedapro") (part "螺丝孔"))
    )
    (comp (ref "SCREW3")
      (value "~")
      (footprint "easyedapro:M3螺丝")
      (libsource (lib "easyedapro") (part "M3螺丝"))
    )
    (comp (ref "SCREW4")
      (value "~")
      (footprint "easyedapro:M3螺丝")
      (libsource (lib "easyedapro") (part "M3螺丝"))
    )
    (comp (ref "SCREW5")
      (value "~")
      (footprint "easyedapro:M3螺丝")
      (libsource (lib "easyedapro") (part "M3螺丝"))
    )
    (comp (ref "SCREW6")
      (value "~")
      (footprint "easyedapro:M3螺丝")
      (libsource (lib "easyedapro") (part "M3螺丝"))
    )
    (comp (ref "SCREW7")
      (value "~")
      (footprint "easyedapro:M3螺丝")
      (libsource (lib "easyedapro") (part "M3螺丝"))
    )
    (comp (ref "SW1")
      (value "SS-12D10L5")
      (footprint "easyedapro:SW-TH_SS-12D10L5")
      (description "电路结构:单刀双掷;安装方式:直插;开关颜色:黑色;额定电流(DC):3A;额定电压(DC):125V;额定电流(AC):3A;额定电压(AC):125V;机械寿命:1万次;")
      (fields (field (name "Manufacturer") "XKB Connectivity(中国星坤)"))
      (libsource (lib "easyedapro") (part "SS-12D10L5"))
    )
    (comp (ref "U1")
      (value "AI8051U-34K64-QFP48")
      (footprint "easyedapro:LQFP-48_L7.0-W7.0-P0.50-LS9.0-BL_1")
      (description "硬件浮点/硬件三角函数 跑100MHz, 32位8051-CPU 跑 42MHz，PWM 有硬件移相功能，DMA支持外设到外设，DMA支持PWM")
      (fields (field (name "Manufacturer") "STC"))
      (libsource (lib "easyedapro") (part "AI8051U-34K64-QFP48"))
    )
    (comp (ref "U2")
      (value "SCT2433STER")
      (footprint "easyedapro:ESOP-8_L4.9-W3.9-P1.27-LS6.0-BL-EP")
      (description "功能类型:降压型;输出类型:可调;工作电压:3.8V~40V;输出电压:800mV~40V;输出电流:3.5A;")
      (fields (field (name "Manufacturer") "SCT(芯洲科技)"))
      (libsource (lib "easyedapro") (part "SCT2433STER"))
    )
    (comp (ref "U3")
      (value "MC7805BDTRKG")
      (footprint "easyedapro:TO-252-2_L6.6-W6.1-P4.57-LS9.9-TL-CW")
      (description "输出类型:固定;最大输入电压:35V;输出电压:5V;最大输出电流:1A;电源纹波抑制比(PSRR):68dB@(120Hz);输出极性:正极;")
      (fields (field (name "Manufacturer") "onsemi(安森美)"))
      (libsource (lib "easyedapro") (part "MC7805BDTRKG"))
    )
    (comp (ref "U4")
      (value "AD8217BRMZ-R7")
      (footprint "easyedapro:MSOP-8_L3.0-W3.0-P0.65-LS5.0-BL")
      (fields (field (name "Manufacturer") "ADI(亚德诺)"))
      (libsource (lib "easyedapro") (part "AD8217BRMZ-R7"))
    )
    (comp (ref "U5")
      (value "IR2184STRPBF")
      (footprint "easyedapro:SOIC-8_L5.0-W4.0-P1.27-LS6.0-BL")
      (description "驱动配置:半桥;负载类型:MOSFET；IGBT;驱动通道数:2;峰值灌电流:2.3A;峰值拉电流:1.9A;电源电压:10V~20V;上升时间:40ns;下降时间:20ns;")
      (fields (field (name "Manufacturer") "Infineon(英飞凌)"))
      (libsource (lib "easyedapro") (part "IR2184STRPBF"))
    )
    (comp (ref "U6")
      (value "IR2184STRPBF")
      (footprint "easyedapro:SOIC-8_L5.0-W4.0-P1.27-LS6.0-BL")
      (description "驱动配置:半桥;负载类型:MOSFET；IGBT;驱动通道数:2;峰值灌电流:2.3A;峰值拉电流:1.9A;电源电压:10V~20V;上升时间:40ns;下降时间:20ns;")
      (fields (field (name "Manufacturer") "Infineon(英飞凌)"))
      (libsource (lib "easyedapro") (part "IR2184STRPBF"))
    )
  )
  (nets
    (net (code "1") (name "+5V") (class "Default")
      (node (ref "C16") (pin "1") (pinfunction "1_1") (pintype "input"))
      (node (ref "C17") (pin "2") (pinfunction "2_2") (pintype "unspecified"))
      (node (ref "C6") (pin "2") (pinfunction "2_2") (pintype "unspecified"))
      (node (ref "C7") (pin "2") (pinfunction "2_2") (pintype "unspecified"))
      (node (ref "H1") (pin "2") (pinfunction "2_2") (pintype "unspecified"))
      (node (ref "H2") (pin "1") (pinfunction "1_1") (pintype "unspecified"))
      (node (ref "R19") (pin "1") (pinfunction "1_1") (pintype "input"))
      (node (ref "R22") (pin "1") (pinfunction "1_1") (pintype "input"))
      (node (ref "R26") (pin "2") (pinfunction "2_2") (pintype "input"))
      (node (ref "R27") (pin "2") (pinfunction "2_2") (pintype "input"))
      (node (ref "U1") (pin "41") (pinfunction "ADC_VRef+/ADC_AVcc/Vcc_41") (pintype "unspecified"))
      (node (ref "U3") (pin "3") (pinfunction "OUT_3") (pintype "unspecified"))
    )
    (net (code "2") (name "+12V") (class "Default")
      (node (ref "C14") (pin "1") (pinfunction "1_1") (pintype "input"))
      (node (ref "C15") (pin "2") (pinfunction "2_2") (pintype "unspecified"))
      (node (ref "C2") (pin "1") (pinfunction "1_1") (pintype "input"))
      (node (ref "C3") (pin "2") (pinfunction "2_2") (pintype "unspecified"))
      (node (ref "C30") (pin "2") (pinfunction "2_2") (pintype "unspecified"))
      (node (ref "C31") (pin "2") (pinfunction "2_2") (pintype "unspecified"))
      (node (ref "C33") (pin "2") (pinfunction "2_2") (pintype "unspecified"))
      (node (ref "C34") (pin "2") (pinfunction "2_2") (pintype "unspecified"))
      (node (ref "C4") (pin "2") (pinfunction "2_2") (pintype "unspecified"))
      (node (ref "D3") (pin "2") (pinfunction "A_2") (pintype "unspecified"))
      (node (ref "D6") (pin "2") (pinfunction "A_2") (pintype "unspecified"))
      (node (ref "L1") (pin "2") (pinfunction "2_2") (pintype "unspecified"))
      (node (ref "R1") (pin "2") (pinfunction "2_2") (pintype "input"))
      (node (ref "R25") (pin "2") (pinfunction "2_2") (pintype "input"))
      (node (ref "U3") (pin "1") (pinfunction "IN_1") (pintype "unspecified"))
      (node (ref "U5") (pin "5") (pinfunction "VCC_5") (pintype "unspecified"))
      (node (ref "U6") (pin "5") (pinfunction "VCC_5") (pintype "unspecified"))
    )
    (net (code "3") (name "+24V") (class "Default")
      (node (ref "C10") (pin "1") (pinfunction "1_1") (pintype "input"))
      (node (ref "C11") (pin "2") (pinfunction "2_2") (pintype "unspecified"))
      (node (ref "C12") (pin "2") (pinfunction "2_2") (pintype "unspecified"))
      (node (ref "C13") (pin "2") (pinfunction "2_2") (pintype "unspecified"))
      (node (ref "C8") (pin "2") (pinfunction "2_2") (pintype "unspecified"))
      (node (ref "FAN1") (pin "1") (pinfunction "1_1") (pintype "unspecified"))
      (node (ref "Q2") (pin "5") (pinfunction "D_5") (pintype "unspecified"))
      (node (ref "R11") (pin "2") (pinfunction "2_2") (pintype "unspecified"))
      (node (ref "R2") (pin "1") (pinfunction "1_1") (pintype "input"))
      (node (ref "R6") (pin "2") (pinfunction "2_2") (pintype "input"))
      (node (ref "U2") (pin "7") (pinfunction "VIN_7") (pintype "unspecified"))
      (node (ref "U4") (pin "1") (pinfunction "+IN_1") (pintype "unspecified"))
    )
    (net (code "4") (name "/ADC1") (class "Default")
      (node (ref "C29") (pin "2") (pinfunction "2_2") (pintype "unspecified"))
      (node (ref "R12") (pin "1") (pinfunction "1_1") (pintype "input"))
      (node (ref "U1") (pin "44") (pinfunction "PWM5_2/PWM1N/CCP2/T2CLKO/ADC1/P1.1_44") (pintype "unspecified"))
    )
    (net (code "5") (name "/ADC_BAT") (class "Default")
      (node (ref "R8") (pin "1") (pinfunction "1_1") (pintype "input"))
      (node (ref "U1") (pin "43") (pinfunction "PWM1P/T2/ADC0/P1.0_43") (pintype "unspecified"))
    )
    (net (code "6") (name "/AGND") (class "Default")
      (node (ref "C29") (pin "1") (pinfunction "1_1") (pintype "unspecified"))
      (node (ref "R29") (pin "2") (pinfunction "2_2") (pintype "input"))
      (node (ref "U4") (pin "4") (pinfunction "GND_4") (pintype "unspecified"))
    )
    (net (code "7") (name "/IO1") (class "Default")
      (node (ref "U1") (pin "38") (pinfunction "PWM2P_2/RxD4/AD2/ADC10/P0.2_38") (pintype "unspecified"))
      (node (ref "U5") (pin "2") (pinfunction "SD_2") (pintype "unspecified"))
      (node (ref "U6") (pin "2") (pinfunction "SD_2") (pintype "unspecified"))
    )
    (net (code "8") (name "/IO2") (class "Default")
      (node (ref "U1") (pin "34") (pinfunction "P0.6/ADC14/AD6/T4/PWM4P_2/PWMFLT_2_34") (pintype "unspecified"))
    )
    (net (code "9") (name "/IO4") (class "Default")
      (node (ref "U1") (pin "35") (pinfunction "P0.5/ADC13/AD5/T3CLKO/PWM3N_2/PWM7_35") (pintype "unspecified"))
    )
    (net (code "10") (name "/KEY0") (class "Default")
      (node (ref "K1") (pin "2") (pinfunction "2_2") (pintype "unspecified"))
      (node (ref "R19") (pin "2") (pinfunction "2_2") (pintype "input"))
      (node (ref "U1") (pin "21") (pinfunction "P2.2/A10/CCP2_3/PWM2P_3/I2SMCLK_3_21") (pintype "unspecified"))
    )
    (net (code "11") (name "/KEY1") (class "Default")
      (node (ref "K2") (pin "2") (pinfunction "2_2") (pintype "unspecified"))
      (node (ref "R22") (pin "2") (pinfunction "2_2") (pintype "input"))
      (node (ref "U1") (pin "19") (pinfunction "P2.0/A8/T11/CCP0_3/PWM1P_3/ADCETR_3/I2SWS_3_19") (pintype "unspecified"))
    )
    (net (code "12") (name "/P0.3") (class "Default")
      (node (ref "U1") (pin "37") (pinfunction "PWM6/PWM2N_2/TxD4/AD3/ADC11/P0.3_37") (pintype "unspecified"))
    )
    (net (code "13") (name "/P0.7") (class "Default")
      (node (ref "U1") (pin "33") (pinfunction "P0.7/AD7/T4CLKO/PWM4N_2/PWM8/PWMFLT_3_33") (pintype "unspecified"))
    )
    (net (code "14") (name "/P1.2") (class "Default")
      (node (ref "H3") (pin "2") (pinfunction "2_2") (pintype "unspecified"))
      (node (ref "R18") (pin "2") (pinfunction "2_2") (pintype "input"))
      (node (ref "U1") (pin "45") (pinfunction "QSPIIO3/PWMETI2_4/PWMETI1_4/PWM2P/ECI/RxD2/ADC2/P1.2_45") (pintype "unspecified"))
    )
    (net (code "15") (name "/P1.3") (class "Default")
      (node (ref "H1") (pin "7") (pinfunction "7_7") (pintype "unspecified"))
      (node (ref "U1") (pin "46") (pinfunction "QSPIIO2/PWM6_2/PWM2N/CCP0/TxD2/ADC3/P1.3_46") (pintype "unspecified"))
    )
    (net (code "16") (name "/P1.4") (class "Default")
      (node (ref "H1") (pin "6") (pinfunction "6_6") (pintype "unspecified"))
      (node (ref "U1") (pin "47") (pinfunction "I2SWS_2/QSPINCS/PWM3P/CCP1/SDA_2/SS/ADC4/P1.4_47") (pintype "unspecified"))
    )
    (net (code "17") (name "/P1.5") (class "Default")
      (node (ref "H1") (pin "5") (pinfunction "5_5") (pintype "unspecified"))
      (node (ref "U1") (pin "2") (pinfunction "I2SSD_2/QSPIIO0/PWM7_2/PWM3N/SCL_2/MOSI/ADC5/P1.5_2") (pintype "unspecified"))
    )
    (net (code "18") (name "/P1.6") (class "Default")
      (node (ref "H1") (pin "4") (pinfunction "4_4") (pintype "unspecified"))
      (node (ref "U1") (pin "3") (pinfunction "I2SMCLK_4/I2SMCLK_2/QSPIIO1/PWM4P/MISO/RxD_3/ADC6/P1.6_3") (pintype "unspecified"))
    )
    (net (code "19") (name "/P1.7") (class "Default")
      (node (ref "H1") (pin "3") (pinfunction "3_3") (pintype "unspecified"))
      (node (ref "U1") (pin "4") (pinfunction "I2SCK_2/QSPICLK/PWM8_2/PWM4N/SCLK/TxD_3/ADC7/P1.7_4") (pintype "unspecified"))
    )
    (net (code "20") (name "/P2.1") (class "Default")
      (node (ref "U1") (pin "20") (pinfunction "P2.1/A9/T11CLKO/CCP1_3/PWM1N_3/PWM5_3/I2SSD_3_20") (pintype "unspecified"))
    )
    (net (code "21") (name "/P2.3") (class "Default")
      (node (ref "U1") (pin "22") (pinfunction "P2.3/A11/SDA/ECI_3/PWM2N_3/PWM6_3/PWM_ETI1_3/PWM_ETI2_3/I2SCK_3_22") (pintype "unspecified"))
    )
    (net (code "22") (name "/P2.4") (class "Default")
      (node (ref "U1") (pin "23") (pinfunction "P2.4/A12/SS_2/SCL/PWM3P_3_23") (pintype "unspecified"))
    )
    (net (code "23") (name "/P2.5") (class "Default")
      (node (ref "U1") (pin "26") (pinfunction "P2.5/A13/MOSI_2/PWM3N_3/PWM7_3/QSPIIO0_3_26") (pintype "unspecified"))
    )
    (net (code "24") (name "/P2.6") (class "Default")
      (node (ref "U1") (pin "27") (pinfunction "P2.6/A14/MISO_2/PWM4P_3/QSPIIO1_3_27") (pintype "unspecified"))
    )
    (net (code "25") (name "/P2.7") (class "Default")
      (node (ref "U1") (pin "28") (pinfunction "P2.7/A15/SCLK_2/PWM4N_3/PWM8_3/QSPICLK_3_28") (pintype "unspecified"))
    )
    (net (code "26") (name "/P3.0") (class "Default")
      (node (ref "H2") (pin "2") (pinfunction "2_2") (pintype "unspecified"))
      (node (ref "U1") (pin "6") (pinfunction "D-/RxD/INT4/P3.0_6") (pintype "unspecified"))
    )
    (net (code "27") (name "/P3.1") (class "Default")
      (node (ref "H2") (pin "3") (pinfunction "3_3") (pintype "unspecified"))
      (node (ref "U1") (pin "8") (pinfunction "D+/TxD/P3.1_8") (pintype "unspecified"))
    )
    (net (code "28") (name "/P3.2") (class "Default")
      (node (ref "U1") (pin "9") (pinfunction "I2SCK/PWM_ETI2/PWM_ETI1/SCL_4/SCLK_4/INT0/P3.2_9") (pintype "unspecified"))
    )
    (net (code "29") (name "/P3.3") (class "Default")
      (node (ref "U1") (pin "10") (pinfunction "PWMAPS5/I2SMCLK/SDA_4/MISO_4/INT1/P3.3_10") (pintype "unspecified"))
    )
    (net (code "30") (name "/P3.4") (class "Default")
      (node (ref "U1") (pin "11") (pinfunction "PWMAPS6/I2SSD/MOSI_4/T1CLKO/T0/P3.4_11") (pintype "unspecified"))
    )
    (net (code "31") (name "/P3.5") (class "Default")
      (node (ref "LED3") (pin "1") (pinfunction "K_1") (pintype "unspecified"))
      (node (ref "U1") (pin "12") (pinfunction "I2SWS/PWMFLT/SS_4/T0CLKO/T1/P3.5_12") (pintype "unspecified"))
    )
    (net (code "32") (name "/P3.6") (class "Default")
      (node (ref "U1") (pin "13") (pinfunction "P3.6/INT2/WR_2/RxD_2_13") (pintype "unspecified"))
    )
    (net (code "33") (name "/P3.7") (class "Default")
      (node (ref "U1") (pin "14") (pinfunction "P3.7/INT3/RD_2/TxD_2_14") (pintype "unspecified"))
    )
    (net (code "34") (name "/P4.0") (class "Default")
      (node (ref "U1") (pin "18") (pinfunction "P4.0/SS_3/ADCETR_2/QSPINCS_2/I2SWS_4_18") (pintype "unspecified"))
    )
    (net (code "35") (name "/P4.1") (class "Default")
      (node (ref "U1") (pin "31") (pinfunction "P4.1/CMPO_2/ECI_2/MOSI_3/PWMETI1_2/PWMETI2_2/QSPIIO0_2/I2SSD_4_31") (pintype "unspecified"))
    )
    (net (code "36") (name "/P4.2") (class "Default")
      (node (ref "U1") (pin "42") (pinfunction "QSPIIO1_2/CCP0_2/MISO_3/RxD2_2/WR/P4.2_42") (pintype "unspecified"))
    )
    (net (code "37") (name "/P4.3") (class "Default")
      (node (ref "U1") (pin "7") (pinfunction "I2SCK_4/QSPICLK_2/CCP1_2/SCLK_3/TxD2_2/RxD_4/P4.3_7") (pintype "unspecified"))
    )
    (net (code "38") (name "/P4.5") (class "Default")
      (node (ref "U1") (pin "30") (pinfunction "P4.5/ALE/CMPO/QSPIIO3_3/P4.4/RD/TxD_4/CCP2_2/PWMAPS5_2/CMP-_30") (pintype "unspecified"))
    )
    (net (code "39") (name "/P4.6") (class "Default")
      (node (ref "U1") (pin "32") (pinfunction "P4.6/CMP+/QSPIIO2_3_32") (pintype "unspecified"))
    )
    (net (code "40") (name "/P4.7") (class "Default")
      (node (ref "U1") (pin "5") (pinfunction "PWMAPS6_2/QSPINCS_3/ADC_ETR/MCLKO/nRST/P4.7_5") (pintype "unspecified"))
    )
    (net (code "41") (name "/P5.0") (class "Default")
      (node (ref "U1") (pin "24") (pinfunction "P5.0/RxD3_2/PWM5_4/CMP+_2_24") (pintype "unspecified"))
    )
    (net (code "42") (name "/P5.1") (class "Default")
      (node (ref "U1") (pin "25") (pinfunction "P5.1/TxD3_2/PWM6_4/CMP+_3_25") (pintype "unspecified"))
    )
    (net (code "43") (name "/P5.2") (class "Default")
      (node (ref "U1") (pin "48") (pinfunction "QSPIIO2_2/PWM7_4/RxD4_2/P5.2_48") (pintype "unspecified"))
    )
    (net (code "44") (name "/P5.3") (class "Default")
      (node (ref "U1") (pin "1") (pinfunction "QSPIIO3_2/PWM8_4/TxD4_2/P5.3_1") (pintype "unspecified"))
    )
    (net (code "45") (name "/P5.6") (class "Default")
      (node (ref "U1") (pin "15") (pinfunction "P5.6/XTALO/MCLKO_2/PWMAPS5_3_15") (pintype "unspecified"))
    )
    (net (code "46") (name "/P5.7") (class "Default")
      (node (ref "U1") (pin "16") (pinfunction "P5.7/XTALI/PWMAPS6_3_16") (pintype "unspecified"))
    )
    (net (code "47") (name "/PWM1N") (class "Default")
      (node (ref "U1") (pin "39") (pinfunction "PWM5/PWM1N_2/TxD3/AD1/ADC9/P0.1_39") (pintype "unspecified"))
    )
    (net (code "48") (name "/PWM1P") (class "Default")
      (node (ref "R15") (pin "2") (pinfunction "2_2") (pintype "input"))
      (node (ref "U1") (pin "40") (pinfunction "PWM1P_2/RxD3/AD0/ADC8/P0.0_40") (pintype "unspecified"))
      (node (ref "U5") (pin "1") (pinfunction "IN_1") (pintype "unspecified"))
    )
    (net (code "49") (name "/PWM3P") (class "Default")
      (node (ref "R23") (pin "2") (pinfunction "2_2") (pintype "input"))
      (node (ref "U1") (pin "36") (pinfunction "P0.4/ADC12/AD4/T3/PWM3P_2_36") (pintype "unspecified"))
      (node (ref "U6") (pin "1") (pinfunction "IN_1") (pintype "unspecified"))
    )
    (net (code "50") (name "/UCAP") (class "Default")
      (node (ref "C9") (pin "1") (pinfunction "1_1") (pintype "unspecified"))
      (node (ref "U1") (pin "29") (pinfunction "UCAP_29") (pintype "unspecified"))
    )
    (net (code "51") (name "GND") (class "Default")
      (node (ref "C14") (pin "2") (pinfunction "2_2") (pintype "input"))
      (node (ref "C15") (pin "1") (pinfunction "1_1") (pintype "unspecified"))
      (node (ref "C16") (pin "2") (pinfunction "2_2") (pintype "input"))
      (node (ref "C17") (pin "1") (pinfunction "1_1") (pintype "unspecified"))
      (node (ref "C6") (pin "1") (pinfunction "1_1") (pintype "unspecified"))
      (node (ref "C7") (pin "1") (pinfunction "1_1") (pintype "unspecified"))
      (node (ref "C9") (pin "2") (pinfunction "2_2") (pintype "unspecified"))
      (node (ref "H1") (pin "1") (pinfunction "1_1") (pintype "unspecified"))
      (node (ref "H2") (pin "4") (pinfunction "4_4") (pintype "unspecified"))
      (node (ref "H3") (pin "1") (pinfunction "1_1") (pintype "unspecified"))
      (node (ref "K1") (pin "1") (pinfunction "1_1") (pintype "unspecified"))
      (node (ref "K2") (pin "1") (pinfunction "1_1") (pintype "unspecified"))
      (node (ref "LED2") (pin "2") (pinfunction "K_2") (pintype "unspecified"))
      (node (ref "R18") (pin "1") (pinfunction "1_1") (pintype "input"))
      (node (ref "R4") (pin "1") (pinfunction "1_1") (pintype "input"))
      (node (ref "R5") (pin "1") (pinfunction "1_1") (pintype "input"))
      (node (ref "R7") (pin "1") (pinfunction "1_1") (pintype "input"))
      (node (ref "R9") (pin "1") (pinfunction "1_1") (pintype "input"))
      (node (ref "U1") (pin "17") (pinfunction "Gnd/ADC_AGnd/ADC_Vref-_17") (pintype "unspecified"))
      (node (ref "U3") (pin "2") (pinfunction "GND_2") (pintype "unspecified"))
    )
    (net (code "52") (name "Net-(CN1-+)") (class "Default")
      (node (ref "CN1") (pin "2") (pinfunction "+_2") (pintype "unspecified"))
      (node (ref "F1") (pin "1") (pinfunction "1_1") (pintype "unspecified"))
    )
    (net (code "53") (name "Net-(CP1-Pad1)") (class "Default")
      (node (ref "CP1") (pin "1") (pinfunction "1_1") (pintype "unspecified"))
      (node (ref "CP10") (pin "1") (pinfunction "1_1") (pintype "unspecified"))
      (node (ref "CP2") (pin "1") (pinfunction "1_1") (pintype "unspecified"))
      (node (ref "CP3") (pin "1") (pinfunction "1_1") (pintype "unspecified"))
      (node (ref "CP4") (pin "1") (pinfunction "1_1") (pintype "unspecified"))
      (node (ref "CP5") (pin "1") (pinfunction "1_1") (pintype "unspecified"))
      (node (ref "CP6") (pin "1") (pinfunction "1_1") (pintype "unspecified"))
      (node (ref "CP7") (pin "1") (pinfunction "1_1") (pintype "unspecified"))
      (node (ref "CP8") (pin "1") (pinfunction "1_1") (pintype "unspecified"))
      (node (ref "CP9") (pin "1") (pinfunction "1_1") (pintype "unspecified"))
      (node (ref "OUT1") (pin "1") (pinfunction "1_1") (pintype "input"))
    )
    (net (code "54") (name "Net-(CP1-Pad2)") (class "Default")
      (node (ref "CP1") (pin "2") (pinfunction "2_2") (pintype "unspecified"))
      (node (ref "CP10") (pin "2") (pinfunction "2_2") (pintype "unspecified"))
      (node (ref "CP2") (pin "2") (pinfunction "2_2") (pintype "unspecified"))
      (node (ref "CP3") (pin "2") (pinfunction "2_2") (pintype "unspecified"))
      (node (ref "CP4") (pin "2") (pinfunction "2_2") (pintype "unspecified"))
      (node (ref "CP5") (pin "2") (pinfunction "2_2") (pintype "unspecified"))
      (node (ref "CP6") (pin "2") (pinfunction "2_2") (pintype "unspecified"))
      (node (ref "CP7") (pin "2") (pinfunction "2_2") (pintype "unspecified"))
      (node (ref "CP8") (pin "2") (pinfunction "2_2") (pintype "unspecified"))
      (node (ref "CP9") (pin "2") (pinfunction "2_2") (pintype "unspecified"))
      (node (ref "CR1") (pin "1") (pinfunction "1_1") (pintype "unspecified"))
      (node (ref "CR10") (pin "2") (pinfunction "2_2") (pintype "unspecified"))
      (node (ref "CR2") (pin "1") (pinfunction "1_1") (pintype "unspecified"))
      (node (ref "CR3") (pin "1") (pinfunction "1_1") (pintype "unspecified"))
      (node (ref "CR4") (pin "2") (pinfunction "2_2") (pintype "unspecified"))
      (node (ref "CR5") (pin "2") (pinfunction "2_2") (pintype "unspecified"))
      (node (ref "CR6") (pin "2") (pinfunction "2_2") (pintype "unspecified"))
      (node (ref "CR7") (pin "2") (pinfunction "2_2") (pintype "unspecified"))
      (node (ref "CR8") (pin "2") (pinfunction "2_2") (pintype "unspecified"))
      (node (ref "CR9") (pin "2") (pinfunction "2_2") (pintype "unspecified"))
      (node (ref "L2") (pin "2") (pinfunction "2_2") (pintype "unspecified"))
    )
    (net (code "55") (name "Net-(D1-A)") (class "Default")
      (node (ref "D1") (pin "2") (pinfunction "A_2") (pintype "unspecified"))
      (node (ref "R10") (pin "1") (pinfunction "1_1") (pintype "input"))
      (node (ref "SW1") (pin "1") (pinfunction "1_1") (pintype "unspecified"))
    )
    (net (code "56") (name "Net-(D2-A)") (class "Default")
      (node (ref "D2") (pin "2") (pinfunction "A_2") (pintype "unspecified"))
      (node (ref "R13") (pin "1") (pinfunction "1_1") (pintype "input"))
    )
    (net (code "57") (name "Net-(D2-C)") (class "Default")
      (node (ref "D2") (pin "1") (pinfunction "C_1") (pintype "unspecified"))
      (node (ref "R14") (pin "1") (pinfunction "1_1") (pintype "input"))
      (node (ref "U5") (pin "7") (pinfunction "HO_7") (pintype "output"))
    )
    (net (code "58") (name "Net-(D3-C)") (class "Default")
      (node (ref "C32") (pin "1") (pinfunction "1_1") (pintype "unspecified"))
      (node (ref "D3") (pin "1") (pinfunction "C_1") (pintype "unspecified"))
      (node (ref "U5") (pin "8") (pinfunction "VB_8") (pintype "unspecified"))
    )
    (net (code "59") (name "Net-(D4-A)") (class "Default")
      (node (ref "D4") (pin "2") (pinfunction "A_2") (pintype "unspecified"))
      (node (ref "R16") (pin "1") (pinfunction "1_1") (pintype "input"))
    )
    (net (code "60") (name "Net-(D4-C)") (class "Default")
      (node (ref "D4") (pin "1") (pinfunction "C_1") (pintype "unspecified"))
      (node (ref "R17") (pin "1") (pinfunction "1_1") (pintype "input"))
      (node (ref "U5") (pin "4") (pinfunction "LO_4") (pintype "unspecified"))
    )
    (net (code "61") (name "Net-(D5-A)") (class "Default")
      (node (ref "D5") (pin "2") (pinfunction "A_2") (pintype "unspecified"))
      (node (ref "R20") (pin "1") (pinfunction "1_1") (pintype "input"))
    )
    (net (code "62") (name "Net-(D5-C)") (class "Default")
      (node (ref "D5") (pin "1") (pinfunction "C_1") (pintype "unspecified"))
      (node (ref "R21") (pin "1") (pinfunction "1_1") (pintype "input"))
      (node (ref "U6") (pin "7") (pinfunction "HO_7") (pintype "output"))
    )
    (net (code "63") (name "Net-(D6-C)") (class "Default")
      (node (ref "C35") (pin "1") (pinfunction "1_1") (pintype "unspecified"))
      (node (ref "D6") (pin "1") (pinfunction "C_1") (pintype "unspecified"))
      (node (ref "U6") (pin "8") (pinfunction "VB_8") (pintype "unspecified"))
    )
    (net (code "64") (name "Net-(D7-A)") (class "Default")
      (node (ref "D7") (pin "2") (pinfunction "A_2") (pintype "unspecified"))
      (node (ref "R24") (pin "1") (pinfunction "1_1") (pintype "input"))
    )
    (net (code "65") (name "Net-(D7-C)") (class "Default")
      (node (ref "D7") (pin "1") (pinfunction "C_1") (pintype "unspecified"))
      (node (ref "R28") (pin "1") (pinfunction "1_1") (pintype "input"))
      (node (ref "U6") (pin "4") (pinfunction "LO_4") (pintype "unspecified"))
    )
    (net (code "66") (name "Net-(LED1-A)") (class "Default")
      (node (ref "LED1") (pin "1") (pinfunction "A_1") (pintype "unspecified"))
      (node (ref "R25") (pin "1") (pinfunction "1_1") (pintype "input"))
    )
    (net (code "67") (name "Net-(LED2-A)") (class "Default")
      (node (ref "LED2") (pin "1") (pinfunction "A_1") (pintype "unspecified"))
      (node (ref "R26") (pin "1") (pinfunction "1_1") (pintype "input"))
    )
    (net (code "68") (name "Net-(LED3-A)") (class "Default")
      (node (ref "LED3") (pin "2") (pinfunction "A_2") (pintype "unspecified"))
      (node (ref "R27") (pin "1") (pinfunction "1_1") (pintype "input"))
    )
    (net (code "69") (name "Net-(Q2-G)") (class "Default")
      (node (ref "Q2") (pin "4") (pinfunction "G_4") (pintype "unspecified"))
      (node (ref "SW1") (pin "2") (pinfunction "2_2") (pintype "unspecified"))
    )
    (net (code "70") (name "Net-(Q3-D)") (class "Default")
      (node (ref "C18") (pin "1") (pinfunction "1_1") (pintype "input"))
      (node (ref "C19") (pin "1") (pinfunction "1_1") (pintype "input"))
      (node (ref "C20") (pin "1") (pinfunction "1_1") (pintype "unspecified"))
      (node (ref "C21") (pin "1") (pinfunction "1_1") (pintype "unspecified"))
      (node (ref "C22") (pin "1") (pinfunction "1_1") (pintype "unspecified"))
      (node (ref "C23") (pin "1") (pinfunction "1_1") (pintype "unspecified"))
      (node (ref "C24") (pin "1") (pinfunction "1_1") (pintype "unspecified"))
      (node (ref "C25") (pin "1") (pinfunction "1_1") (pintype "unspecified"))
      (node (ref "C26") (pin "1") (pinfunction "1_1") (pintype "unspecified"))
      (node (ref "C27") (pin "1") (pinfunction "1_1") (pintype "unspecified"))
      (node (ref "C28") (pin "1") (pinfunction "1_1") (pintype "unspecified"))
      (node (ref "Q3") (pin "9") (pinfunction "D_9") (pintype "unspecified"))
      (node (ref "Q5") (pin "9") (pinfunction "D_9") (pintype "unspecified"))
      (node (ref "R11") (pin "1") (pinfunction "1_1") (pintype "unspecified"))
      (node (ref "U4") (pin "8") (pinfunction "-IN_8") (pintype "unspecified"))
    )
    (net (code "71") (name "Net-(Q3-G)") (class "Default")
      (node (ref "Q3") (pin "1") (pinfunction "G_1") (pintype "unspecified"))
      (node (ref "R13") (pin "2") (pinfunction "2_2") (pintype "input"))
      (node (ref "R14") (pin "2") (pinfunction "2_2") (pintype "input"))
    )
    (net (code "72") (name "Net-(Q4-G)") (class "Default")
      (node (ref "Q4") (pin "1") (pinfunction "G_1") (pintype "unspecified"))
      (node (ref "R16") (pin "2") (pinfunction "2_2") (pintype "input"))
      (node (ref "R17") (pin "2") (pinfunction "2_2") (pintype "input"))
    )
    (net (code "73") (name "Net-(Q5-G)") (class "Default")
      (node (ref "Q5") (pin "1") (pinfunction "G_1") (pintype "unspecified"))
      (node (ref "R20") (pin "2") (pinfunction "2_2") (pintype "input"))
      (node (ref "R21") (pin "2") (pinfunction "2_2") (pintype "input"))
    )
    (net (code "74") (name "Net-(Q6-G)") (class "Default")
      (node (ref "Q6") (pin "1") (pinfunction "G_1") (pintype "unspecified"))
      (node (ref "R24") (pin "2") (pinfunction "2_2") (pintype "input"))
      (node (ref "R28") (pin "2") (pinfunction "2_2") (pintype "input"))
    )
    (net (code "75") (name "Net-(R6-Pad1)") (class "Default")
      (node (ref "R6") (pin "1") (pinfunction "1_1") (pintype "input"))
      (node (ref "R8") (pin "2") (pinfunction "2_2") (pintype "input"))
      (node (ref "R9") (pin "2") (pinfunction "2_2") (pintype "input"))
    )
    (net (code "76") (name "Net-(U2-BOOT)") (class "Default")
      (node (ref "C1") (pin "2") (pinfunction "2_2") (pintype "unspecified"))
      (node (ref "U2") (pin "1") (pinfunction "BOOT_1") (pintype "unspecified"))
    )
    (net (code "77") (name "Net-(U2-EN)") (class "Default")
      (node (ref "R2") (pin "2") (pinfunction "2_2") (pintype "input"))
      (node (ref "U2") (pin "5") (pinfunction "EN_5") (pintype "unspecified"))
    )
    (net (code "78") (name "Net-(U2-FB)") (class "Default")
      (node (ref "R1") (pin "1") (pinfunction "1_1") (pintype "input"))
      (node (ref "R3") (pin "2") (pinfunction "2_2") (pintype "input"))
      (node (ref "U2") (pin "4") (pinfunction "FB_4") (pintype "unspecified"))
    )
    (net (code "79") (name "Net-(U2-SW)") (class "Default")
      (node (ref "C1") (pin "1") (pinfunction "1_1") (pintype "unspecified"))
      (node (ref "L1") (pin "1") (pinfunction "1_1") (pintype "unspecified"))
      (node (ref "U2") (pin "8") (pinfunction "SW_8") (pintype "unspecified"))
    )
    (net (code "80") (name "Net-(U4-OUT)") (class "Default")
      (node (ref "R12") (pin "2") (pinfunction "2_2") (pintype "input"))
      (node (ref "U4") (pin "5") (pinfunction "OUT_5") (pintype "unspecified"))
    )
    (net (code "81") (name "OUT1") (class "Default")
      (node (ref "C35") (pin "2") (pinfunction "2_2") (pintype "unspecified"))
      (node (ref "L2") (pin "1") (pinfunction "1_1") (pintype "unspecified"))
      (node (ref "Q5") (pin "2") (pinfunction "S_2") (pintype "unspecified"))
      (node (ref "Q5") (pin "3") (pinfunction "S_3") (pintype "unspecified"))
      (node (ref "Q5") (pin "4") (pinfunction "S_4") (pintype "unspecified"))
      (node (ref "Q5") (pin "5") (pinfunction "S_5") (pintype "unspecified"))
      (node (ref "Q5") (pin "6") (pinfunction "S_6") (pintype "unspecified"))
      (node (ref "Q5") (pin "7") (pinfunction "S_7") (pintype "unspecified"))
      (node (ref "Q5") (pin "8") (pinfunction "S_8") (pintype "unspecified"))
      (node (ref "Q6") (pin "9") (pinfunction "D_9") (pintype "unspecified"))
      (node (ref "U6") (pin "6") (pinfunction "VS_6") (pintype "unspecified"))
    )
    (net (code "82") (name "OUT2") (class "Default")
      (node (ref "C32") (pin "2") (pinfunction "2_2") (pintype "unspecified"))
      (node (ref "CR1") (pin "2") (pinfunction "2_2") (pintype "unspecified"))
      (node (ref "CR10") (pin "1") (pinfunction "1_1") (pintype "unspecified"))
      (node (ref "CR2") (pin "2") (pinfunction "2_2") (pintype "unspecified"))
      (node (ref "CR3") (pin "2") (pinfunction "2_2") (pintype "unspecified"))
      (node (ref "CR4") (pin "1") (pinfunction "1_1") (pintype "unspecified"))
      (node (ref "CR5") (pin "1") (pinfunction "1_1") (pintype "unspecified"))
      (node (ref "CR6") (pin "1") (pinfunction "1_1") (pintype "unspecified"))
      (node (ref "CR7") (pin "1") (pinfunction "1_1") (pintype "unspecified"))
      (node (ref "CR8") (pin "1") (pinfunction "1_1") (pintype "unspecified"))
      (node (ref "CR9") (pin "1") (pinfunction "1_1") (pintype "unspecified"))
      (node (ref "OUT2") (pin "1") (pinfunction "1_1") (pintype "input"))
      (node (ref "Q3") (pin "2") (pinfunction "S_2") (pintype "unspecified"))
      (node (ref "Q3") (pin "3") (pinfunction "S_3") (pintype "unspecified"))
      (node (ref "Q3") (pin "4") (pinfunction "S_4") (pintype "unspecified"))
      (node (ref "Q3") (pin "5") (pinfunction "S_5") (pintype "unspecified"))
      (node (ref "Q3") (pin "6") (pinfunction "S_6") (pintype "unspecified"))
      (node (ref "Q3") (pin "7") (pinfunction "S_7") (pintype "unspecified"))
      (node (ref "Q3") (pin "8") (pinfunction "S_8") (pintype "unspecified"))
      (node (ref "Q4") (pin "9") (pinfunction "D_9") (pintype "unspecified"))
      (node (ref "U5") (pin "6") (pinfunction "VS_6") (pintype "unspecified"))
    )
    (net (code "83") (name "PGND") (class "Default")
      (node (ref "C10") (pin "2") (pinfunction "2_2") (pintype "input"))
      (node (ref "C11") (pin "1") (pinfunction "1_1") (pintype "unspecified"))
      (node (ref "C12") (pin "1") (pinfunction "1_1") (pintype "unspecified"))
      (node (ref "C13") (pin "1") (pinfunction "1_1") (pintype "unspecified"))
      (node (ref "C18") (pin "2") (pinfunction "2_2") (pintype "input"))
      (node (ref "C19") (pin "2") (pinfunction "2_2") (pintype "input"))
      (node (ref "C2") (pin "2") (pinfunction "2_2") (pintype "input"))
      (node (ref "C20") (pin "2") (pinfunction "2_2") (pintype "unspecified"))
      (node (ref "C21") (pin "2") (pinfunction "2_2") (pintype "unspecified"))
      (node (ref "C22") (pin "2") (pinfunction "2_2") (pintype "unspecified"))
      (node (ref "C23") (pin "2") (pinfunction "2_2") (pintype "unspecified"))
      (node (ref "C24") (pin "2") (pinfunction "2_2") (pintype "unspecified"))
      (node (ref "C25") (pin "2") (pinfunction "2_2") (pintype "unspecified"))
      (node (ref "C26") (pin "2") (pinfunction "2_2") (pintype "unspecified"))
      (node (ref "C27") (pin "2") (pinfunction "2_2") (pintype "unspecified"))
      (node (ref "C28") (pin "2") (pinfunction "2_2") (pintype "unspecified"))
      (node (ref "C3") (pin "1") (pinfunction "1_1") (pintype "unspecified"))
      (node (ref "C30") (pin "1") (pinfunction "1_1") (pintype "unspecified"))
      (node (ref "C31") (pin "1") (pinfunction "1_1") (pintype "unspecified"))
      (node (ref "C33") (pin "1") (pinfunction "1_1") (pintype "unspecified"))
      (node (ref "C34") (pin "1") (pinfunction "1_1") (pintype "unspecified"))
      (node (ref "C4") (pin "1") (pinfunction "1_1") (pintype "unspecified"))
      (node (ref "C8") (pin "1") (pinfunction "1_1") (pintype "unspecified"))
      (node (ref "CN1") (pin "1") (pinfunction "-_1") (pintype "unspecified"))
      (node (ref "FAN1") (pin "2") (pinfunction "2_2") (pintype "unspecified"))
      (node (ref "LED1") (pin "2") (pinfunction "K_2") (pintype "unspecified"))
      (node (ref "Q4") (pin "2") (pinfunction "S_2") (pintype "unspecified"))
      (node (ref "Q4") (pin "3") (pinfunction "S_3") (pintype "unspecified"))
      (node (ref "Q4") (pin "4") (pinfunction "S_4") (pintype "unspecified"))
      (node (ref "Q4") (pin "5") (pinfunction "S_5") (pintype "unspecified"))
      (node (ref "Q4") (pin "6") (pinfunction "S_6") (pintype "unspecified"))
      (node (ref "Q4") (pin "7") (pinfunction "S_7") (pintype "unspecified"))
      (node (ref "Q4") (pin "8") (pinfunction "S_8") (pintype "unspecified"))
      (node (ref "Q6") (pin "2") (pinfunction "S_2") (pintype "unspecified"))
      (node (ref "Q6") (pin "3") (pinfunction "S_3") (pintype "unspecified"))
      (node (ref "Q6") (pin "4") (pinfunction "S_4") (pintype "unspecified"))
      (node (ref "Q6") (pin "5") (pinfunction "S_5") (pintype "unspecified"))
      (node (ref "Q6") (pin "6") (pinfunction "S_6") (pintype "unspecified"))
      (node (ref "Q6") (pin "7") (pinfunction "S_7") (pintype "unspecified"))
      (node (ref "Q6") (pin "8") (pinfunction "S_8") (pintype "unspecified"))
      (node (ref "R10") (pin "2") (pinfunction "2_2") (pintype "input"))
      (node (ref "R15") (pin "1") (pinfunction "1_1") (pintype "input"))
      (node (ref "R23") (pin "1") (pinfunction "1_1") (pintype "input"))
      (node (ref "R29") (pin "1") (pinfunction "1_1") (pintype "input"))
      (node (ref "R3") (pin "1") (pinfunction "1_1") (pintype "input"))
      (node (ref "R4") (pin "2") (pinfunction "2_2") (pintype "input"))
      (node (ref "R5") (pin "2") (pinfunction "2_2") (pintype "input"))
      (node (ref "R7") (pin "2") (pinfunction "2_2") (pintype "input"))
      (node (ref "U2") (pin "6") (pinfunction "GND_6") (pintype "unspecified"))
      (node (ref "U2") (pin "9") (pinfunction "EP_9") (pintype "unspecified"))
      (node (ref "U5") (pin "3") (pinfunction "COM_3") (pintype "unspecified"))
      (node (ref "U6") (pin "3") (pinfunction "COM_3") (pintype "unspecified"))
    )
    (net (code "84") (name "VIN") (class "Default")
      (node (ref "D1") (pin "1") (pinfunction "K_1") (pintype "unspecified"))
      (node (ref "F1") (pin "2") (pinfunction "2_2") (pintype "unspecified"))
      (node (ref "Q2") (pin "1") (pinfunction "S_1") (pintype "unspecified"))
      (node (ref "Q2") (pin "2") (pinfunction "S_2") (pintype "unspecified"))
      (node (ref "Q2") (pin "3") (pinfunction "S_3") (pintype "unspecified"))
      (node (ref "SW1") (pin "3") (pinfunction "3_3") (pintype "unspecified"))
    )
    (net (code "85") (name "unconnected-(CN1-Pad3)") (class "Default")
      (node (ref "CN1") (pin "3") (pinfunction "3_3") (pintype "unspecified+no_connect"))
    )
    (net (code "86") (name "unconnected-(CN1-Pad4)") (class "Default")
      (node (ref "CN1") (pin "4") (pinfunction "4_4") (pintype "unspecified+no_connect"))
    )
    (net (code "87") (name "unconnected-(L2-Pad3)") (class "Default")
      (node (ref "L2") (pin "3") (pinfunction "3_3") (pintype "unspecified+no_connect"))
    )
    (net (code "88") (name "unconnected-(SCREW1-Pad1)") (class "Default")
      (node (ref "SCREW1") (pin "1") (pinfunction "1_1") (pintype "input+no_connect"))
    )
    (net (code "89") (name "unconnected-(SCREW2-Pad1)") (class "Default")
      (node (ref "SCREW2") (pin "1") (pinfunction "1_1") (pintype "input+no_connect"))
    )
    (net (code "90") (name "unconnected-(SCREW3-Pad1)") (class "Default")
      (node (ref "SCREW3") (pin "1") (pinfunction "1_1") (pintype "input+no_connect"))
    )
    (net (code "91") (name "unconnected-(SCREW4-Pad1)") (class "Default")
      (node (ref "SCREW4") (pin "1") (pinfunction "1_1") (pintype "input+no_connect"))
    )
    (net (code "92") (name "unconnected-(SCREW5-Pad1)") (class "Default")
      (node (ref "SCREW5") (pin "1") (pinfunction "1_1") (pintype "input+no_connect"))
    )
    (net (code "93") (name "unconnected-(SCREW6-Pad1)") (class "Default")
      (node (ref "SCREW6") (pin "1") (pinfunction "1_1") (pintype "input+no_connect"))
    )
    (net (code "94") (name "unconnected-(SCREW7-Pad1)") (class "Default")
      (node (ref "SCREW7") (pin "1") (pinfunction "1_1") (pintype "input+no_connect"))
    )
    (net (code "95") (name "unconnected-(U2-NC-Pad2)") (class "Default")
      (node (ref "U2") (pin "2") (pinfunction "NC_2") (pintype "unspecified+no_connect"))
    )
    (net (code "96") (name "unconnected-(U2-NC-Pad3)") (class "Default")
      (node (ref "U2") (pin "3") (pinfunction "NC_3") (pintype "unspecified+no_connect"))
    )
    (net (code "97") (name "unconnected-(U4-NC-Pad7)") (class "Default")
      (node (ref "U4") (pin "7") (pinfunction "NC_7") (pintype "unspecified+no_connect"))
    )
    (net (code "98") (name "unconnected-(U4-NC{slash}2-Pad2)") (class "Default")
      (node (ref "U4") (pin "2") (pinfunction "NC/2_2") (pintype "unspecified+no_connect"))
    )
    (net (code "99") (name "unconnected-(U4-NC{slash}3-Pad6)") (class "Default")
      (node (ref "U4") (pin "6") (pinfunction "NC/3_6") (pintype "unspecified+no_connect"))
    )
    (net (code "100") (name "unconnected-(U4-NC{slash}4-Pad3)") (class "Default")
      (node (ref "U4") (pin "3") (pinfunction "NC/4_3") (pintype "unspecified+no_connect"))
    )
  )
)
